# Main.net
KiCad netlist of a schematic drawn in Altium Designer
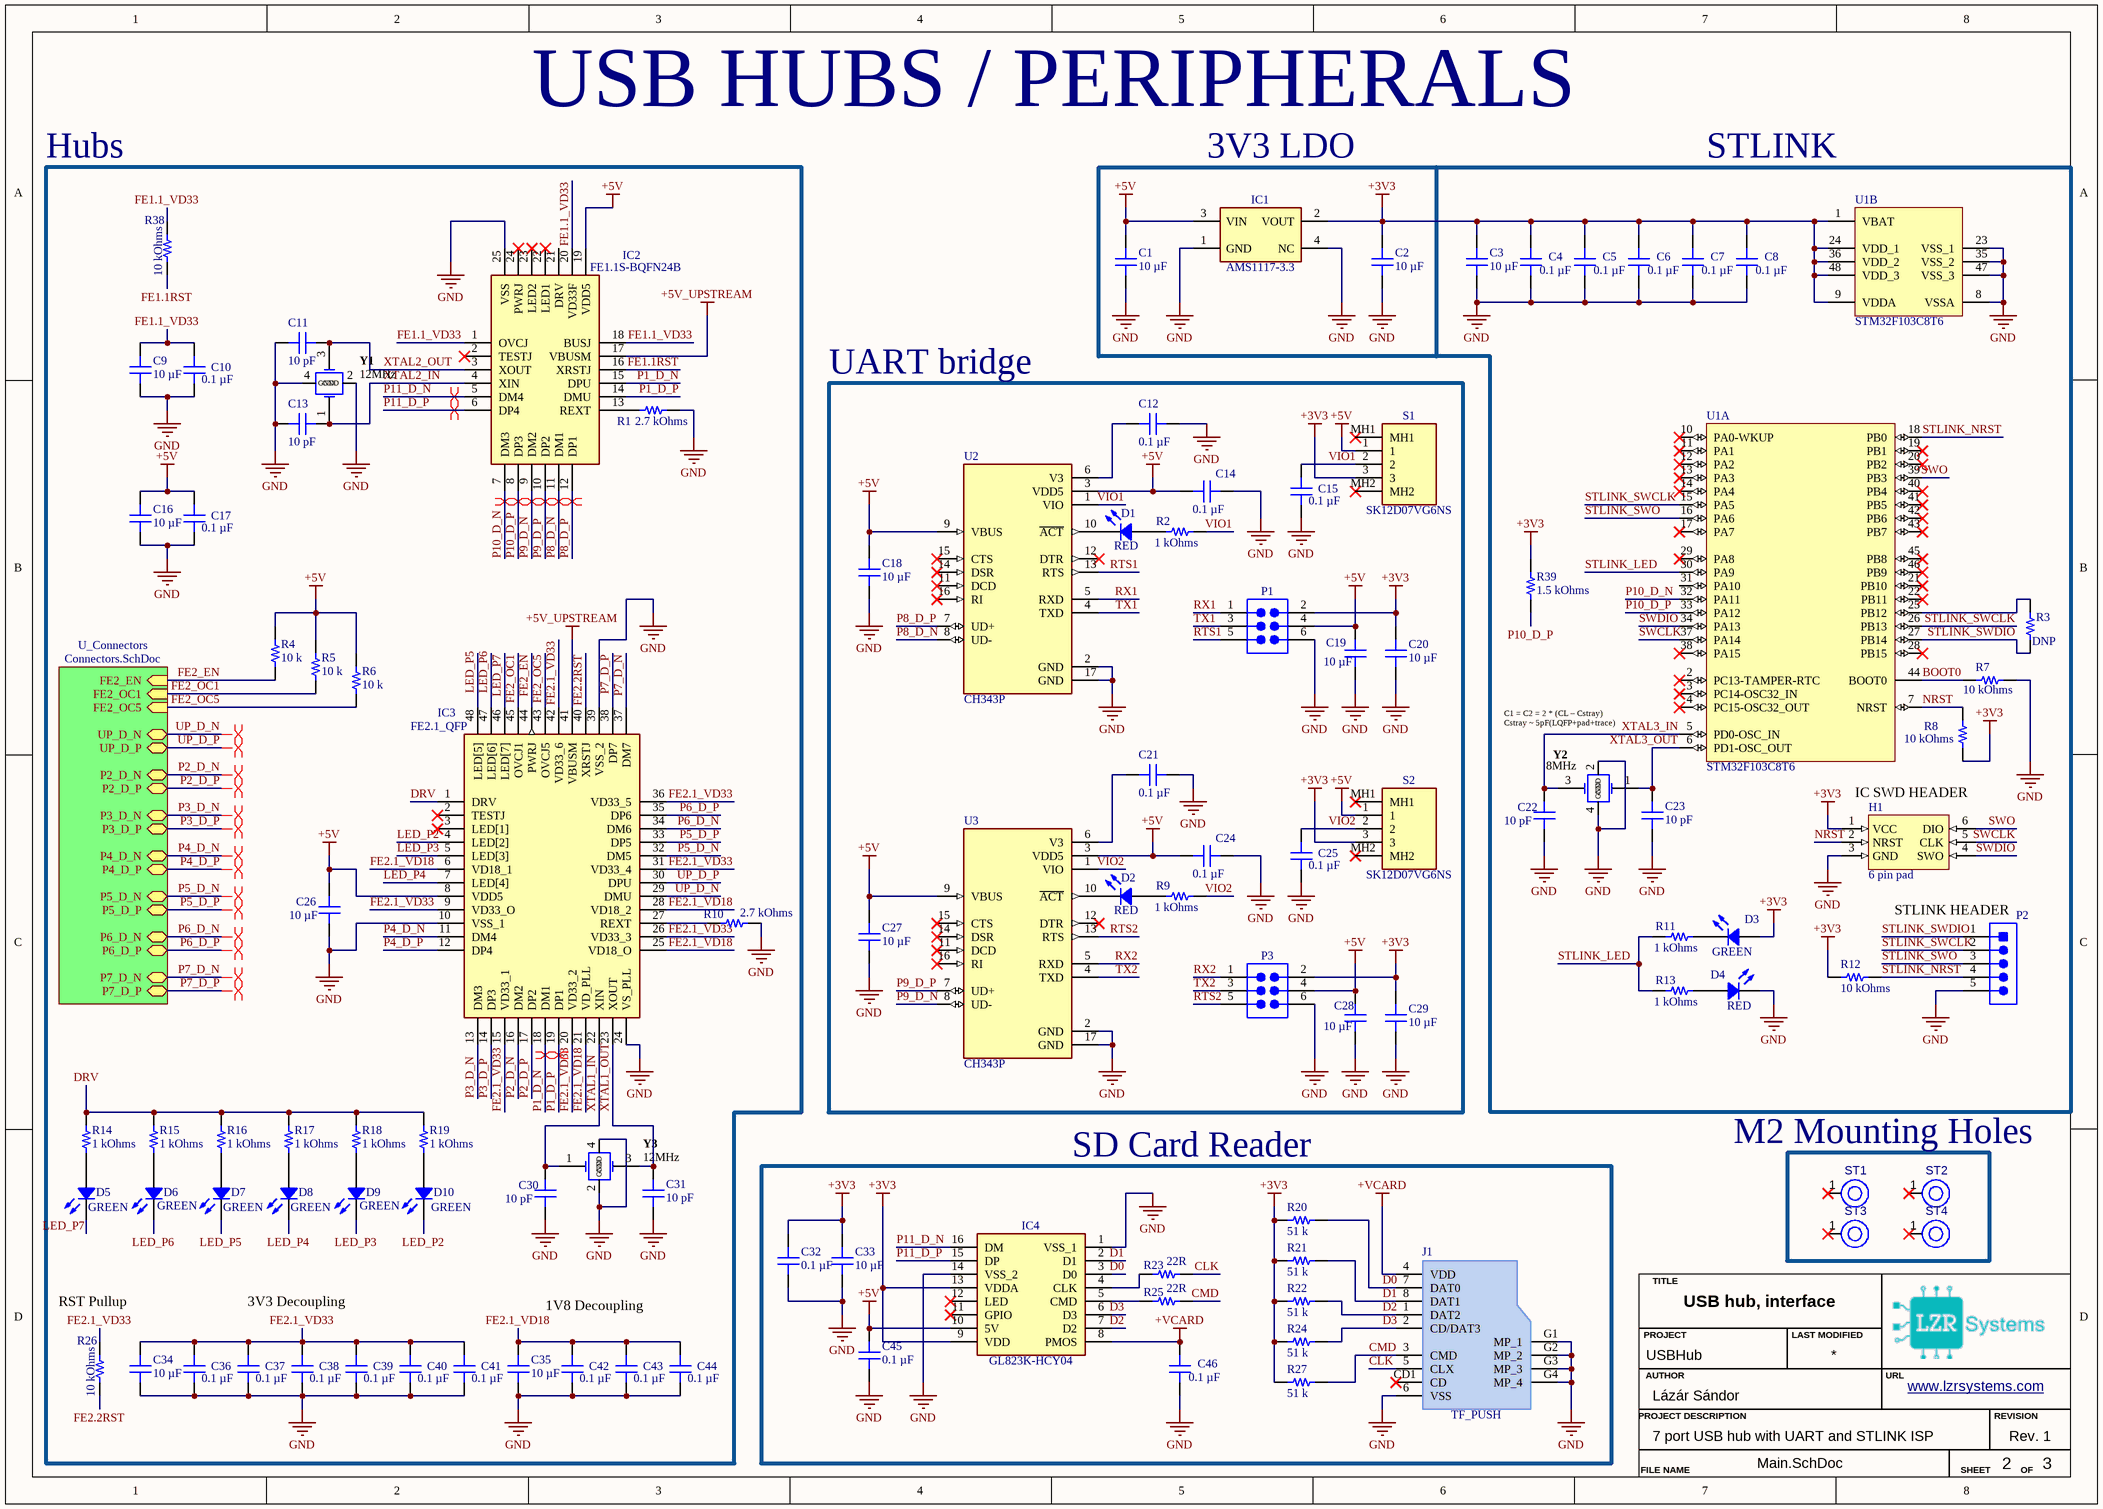
[diagram p0: Main.SchDoc]

(export (version "E")
  (design (tool "Eeschema 10.0.6"))
  (components
    (comp (ref "C1")
      (value "10 µF")
      (footprint "MURATA GRM21B 0805_2012")
      (description "CAP CER 10UF 25V X5R 0805")
      (fields
        (field (name "PART NUMBER") "GRM21BR61E106KA73K")
        (field (name "CAPACITANCE") "10 µF")
        (field (name "MANUFACTURER") "Murata Electronics")
      )
      (libsource (lib "Celestial Altium Library - altium_library") (part "Capacitor"))
    )
    (comp (ref "C2")
      (value "10 µF")
      (footprint "MURATA GRM21B 0805_2012")
      (description "CAP CER 10UF 25V X5R 0805")
      (fields
        (field (name "PART NUMBER") "GRM21BR61E106KA73K")
        (field (name "CAPACITANCE") "10 µF")
        (field (name "MANUFACTURER") "Murata Electronics")
      )
      (libsource (lib "Celestial Altium Library - altium_library") (part "Capacitor"))
    )
    (comp (ref "C3")
      (value "10 µF")
      (footprint "MURATA GRM21B 0805_2012")
      (description "CAP CER 10UF 25V X5R 0805")
      (fields
        (field (name "PART NUMBER") "GRM21BR61E106KA73K")
        (field (name "CAPACITANCE") "10 µF")
        (field (name "MANUFACTURER") "Murata Electronics")
      )
      (libsource (lib "Celestial Altium Library - altium_library") (part "Capacitor"))
    )
    (comp (ref "C4")
      (value "0.1 µF")
      (footprint "CAP 0603_1608")
      (description "CAP CER 0.1UF 50V X7R 0603")
      (fields
        (field (name "PART NUMBER") "GCJ188R71H104KA12D")
        (field (name "CAPACITANCE") "0.1 µF")
        (field (name "MANUFACTURER") "Murata Electronics")
      )
      (libsource (lib "Celestial Altium Library - altium_library") (part "Capacitor"))
    )
    (comp (ref "C5")
      (value "0.1 µF")
      (footprint "CAP 0603_1608")
      (description "CAP CER 0.1UF 50V X7R 0603")
      (fields
        (field (name "PART NUMBER") "GCJ188R71H104KA12D")
        (field (name "CAPACITANCE") "0.1 µF")
        (field (name "MANUFACTURER") "Murata Electronics")
      )
      (libsource (lib "Celestial Altium Library - altium_library") (part "Capacitor"))
    )
    (comp (ref "C6")
      (value "0.1 µF")
      (footprint "CAP 0603_1608")
      (description "CAP CER 0.1UF 50V X7R 0603")
      (fields
        (field (name "PART NUMBER") "GCJ188R71H104KA12D")
        (field (name "CAPACITANCE") "0.1 µF")
        (field (name "MANUFACTURER") "Murata Electronics")
      )
      (libsource (lib "Celestial Altium Library - altium_library") (part "Capacitor"))
    )
    (comp (ref "C7")
      (value "0.1 µF")
      (footprint "CAP 0603_1608")
      (description "CAP CER 0.1UF 50V X7R 0603")
      (fields
        (field (name "PART NUMBER") "GCJ188R71H104KA12D")
        (field (name "CAPACITANCE") "0.1 µF")
        (field (name "MANUFACTURER") "Murata Electronics")
      )
      (libsource (lib "Celestial Altium Library - altium_library") (part "Capacitor"))
    )
    (comp (ref "C8")
      (value "0.1 µF")
      (footprint "CAP 0603_1608")
      (description "CAP CER 0.1UF 50V X7R 0603")
      (fields
        (field (name "PART NUMBER") "GCJ188R71H104KA12D")
        (field (name "CAPACITANCE") "0.1 µF")
        (field (name "MANUFACTURER") "Murata Electronics")
      )
      (libsource (lib "Celestial Altium Library - altium_library") (part "Capacitor"))
    )
    (comp (ref "C9")
      (value "10 µF")
      (footprint "MURATA GRM21B 0805_2012")
      (description "CAP CER 10UF 25V X5R 0805")
      (fields
        (field (name "PART NUMBER") "GRM21BR61E106KA73K")
        (field (name "CAPACITANCE") "10 µF")
        (field (name "MANUFACTURER") "Murata Electronics")
      )
      (libsource (lib "Celestial Altium Library - altium_library") (part "Capacitor"))
    )
    (comp (ref "C10")
      (value "0.1 µF")
      (footprint "CAP 0603_1608")
      (description "CAP CER 0.1UF 50V X7R 0603")
      (fields
        (field (name "PART NUMBER") "GCJ188R71H104KA12D")
        (field (name "CAPACITANCE") "0.1 µF")
        (field (name "MANUFACTURER") "Murata Electronics")
      )
      (libsource (lib "Celestial Altium Library - altium_library") (part "Capacitor"))
    )
    (comp (ref "C11")
      (value "10 pF")
      (footprint "MURATA GCM188 0603_1608")
      (description "CAP CER 10PF 100V C0G/NP0 0603")
      (fields
        (field (name "PART NUMBER") "GCM1885C2A100FA16D")
        (field (name "CAPACITANCE") "10 pF")
        (field (name "MANUFACTURER") "Murata Electronics")
      )
      (libsource (lib "Celestial Altium Library - altium_library") (part "Capacitor"))
    )
    (comp (ref "C12")
      (value "0.1 µF")
      (footprint "CAP 0603_1608")
      (description "CAP CER 0.1UF 50V X7R 0603")
      (fields
        (field (name "PART NUMBER") "GCJ188R71H104KA12D")
        (field (name "CAPACITANCE") "0.1 µF")
        (field (name "MANUFACTURER") "Murata Electronics")
      )
      (libsource (lib "Celestial Altium Library - altium_library") (part "Capacitor"))
    )
    (comp (ref "C13")
      (value "10 pF")
      (footprint "MURATA GCM188 0603_1608")
      (description "CAP CER 10PF 100V C0G/NP0 0603")
      (fields
        (field (name "PART NUMBER") "GCM1885C2A100FA16D")
        (field (name "CAPACITANCE") "10 pF")
        (field (name "MANUFACTURER") "Murata Electronics")
      )
      (libsource (lib "Celestial Altium Library - altium_library") (part "Capacitor"))
    )
    (comp (ref "C14")
      (value "0.1 µF")
      (footprint "CAP 0603_1608")
      (description "CAP CER 0.1UF 50V X7R 0603")
      (fields
        (field (name "PART NUMBER") "GCJ188R71H104KA12D")
        (field (name "CAPACITANCE") "0.1 µF")
        (field (name "MANUFACTURER") "Murata Electronics")
      )
      (libsource (lib "Celestial Altium Library - altium_library") (part "Capacitor"))
    )
    (comp (ref "C15")
      (value "0.1 µF")
      (footprint "CAP 0603_1608")
      (description "CAP CER 0.1UF 50V X7R 0603")
      (fields
        (field (name "PART NUMBER") "GCJ188R71H104KA12D")
        (field (name "CAPACITANCE") "0.1 µF")
        (field (name "MANUFACTURER") "Murata Electronics")
      )
      (libsource (lib "Celestial Altium Library - altium_library") (part "Capacitor"))
    )
    (comp (ref "C16")
      (value "10 µF")
      (footprint "MURATA GRM21B 0805_2012")
      (description "CAP CER 10UF 25V X5R 0805")
      (fields
        (field (name "PART NUMBER") "GRM21BR61E106KA73K")
        (field (name "CAPACITANCE") "10 µF")
        (field (name "MANUFACTURER") "Murata Electronics")
      )
      (libsource (lib "Celestial Altium Library - altium_library") (part "Capacitor"))
    )
    (comp (ref "C17")
      (value "0.1 µF")
      (footprint "CAP 0603_1608")
      (description "CAP CER 0.1UF 50V X7R 0603")
      (fields
        (field (name "PART NUMBER") "GCJ188R71H104KA12D")
        (field (name "CAPACITANCE") "0.1 µF")
        (field (name "MANUFACTURER") "Murata Electronics")
      )
      (libsource (lib "Celestial Altium Library - altium_library") (part "Capacitor"))
    )
    (comp (ref "C18")
      (value "10 µF")
      (footprint "MURATA GRM21B 0805_2012")
      (description "CAP CER 10UF 25V X5R 0805")
      (fields
        (field (name "PART NUMBER") "GRM21BR61E106KA73K")
        (field (name "CAPACITANCE") "10 µF")
        (field (name "MANUFACTURER") "Murata Electronics")
      )
      (libsource (lib "Celestial Altium Library - altium_library") (part "Capacitor"))
    )
    (comp (ref "C19")
      (value "10 µF")
      (footprint "MURATA GRM21B 0805_2012")
      (description "CAP CER 10UF 25V X5R 0805")
      (fields
        (field (name "PART NUMBER") "GRM21BR61E106KA73K")
        (field (name "CAPACITANCE") "10 µF")
        (field (name "MANUFACTURER") "Murata Electronics")
      )
      (libsource (lib "Celestial Altium Library - altium_library") (part "Capacitor"))
    )
    (comp (ref "C20")
      (value "10 µF")
      (footprint "MURATA GRM21B 0805_2012")
      (description "CAP CER 10UF 25V X5R 0805")
      (fields
        (field (name "PART NUMBER") "GRM21BR61E106KA73K")
        (field (name "CAPACITANCE") "10 µF")
        (field (name "MANUFACTURER") "Murata Electronics")
      )
      (libsource (lib "Celestial Altium Library - altium_library") (part "Capacitor"))
    )
    (comp (ref "C21")
      (value "0.1 µF")
      (footprint "CAP 0603_1608")
      (description "CAP CER 0.1UF 50V X7R 0603")
      (fields
        (field (name "PART NUMBER") "GCJ188R71H104KA12D")
        (field (name "CAPACITANCE") "0.1 µF")
        (field (name "MANUFACTURER") "Murata Electronics")
      )
      (libsource (lib "Celestial Altium Library - altium_library") (part "Capacitor"))
    )
    (comp (ref "C22")
      (value "10 pF")
      (footprint "MURATA GCM188 0603_1608")
      (description "CAP CER 10PF 100V C0G/NP0 0603")
      (fields
        (field (name "PART NUMBER") "GCM1885C2A100FA16D")
        (field (name "CAPACITANCE") "10 pF")
        (field (name "MANUFACTURER") "Murata Electronics")
      )
      (libsource (lib "Celestial Altium Library - altium_library") (part "Capacitor"))
    )
    (comp (ref "C23")
      (value "10 pF")
      (footprint "MURATA GCM188 0603_1608")
      (description "CAP CER 10PF 100V C0G/NP0 0603")
      (fields
        (field (name "PART NUMBER") "GCM1885C2A100FA16D")
        (field (name "CAPACITANCE") "10 pF")
        (field (name "MANUFACTURER") "Murata Electronics")
      )
      (libsource (lib "Celestial Altium Library - altium_library") (part "Capacitor"))
    )
    (comp (ref "C24")
      (value "0.1 µF")
      (footprint "CAP 0603_1608")
      (description "CAP CER 0.1UF 50V X7R 0603")
      (fields
        (field (name "PART NUMBER") "GCJ188R71H104KA12D")
        (field (name "CAPACITANCE") "0.1 µF")
        (field (name "MANUFACTURER") "Murata Electronics")
      )
      (libsource (lib "Celestial Altium Library - altium_library") (part "Capacitor"))
    )
    (comp (ref "C25")
      (value "0.1 µF")
      (footprint "CAP 0603_1608")
      (description "CAP CER 0.1UF 50V X7R 0603")
      (fields
        (field (name "PART NUMBER") "GCJ188R71H104KA12D")
        (field (name "CAPACITANCE") "0.1 µF")
        (field (name "MANUFACTURER") "Murata Electronics")
      )
      (libsource (lib "Celestial Altium Library - altium_library") (part "Capacitor"))
    )
    (comp (ref "C26")
      (value "10 µF")
      (footprint "MURATA GRM21B 0805_2012")
      (description "CAP CER 10UF 25V X5R 0805")
      (fields
        (field (name "PART NUMBER") "GRM21BR61E106KA73K")
        (field (name "CAPACITANCE") "10 µF")
        (field (name "MANUFACTURER") "Murata Electronics")
      )
      (libsource (lib "Celestial Altium Library - altium_library") (part "Capacitor"))
    )
    (comp (ref "C27")
      (value "10 µF")
      (footprint "MURATA GRM21B 0805_2012")
      (description "CAP CER 10UF 25V X5R 0805")
      (fields
        (field (name "PART NUMBER") "GRM21BR61E106KA73K")
        (field (name "CAPACITANCE") "10 µF")
        (field (name "MANUFACTURER") "Murata Electronics")
      )
      (libsource (lib "Celestial Altium Library - altium_library") (part "Capacitor"))
    )
    (comp (ref "C28")
      (value "10 µF")
      (footprint "MURATA GRM21B 0805_2012")
      (description "CAP CER 10UF 25V X5R 0805")
      (fields
        (field (name "PART NUMBER") "GRM21BR61E106KA73K")
        (field (name "CAPACITANCE") "10 µF")
        (field (name "MANUFACTURER") "Murata Electronics")
      )
      (libsource (lib "Celestial Altium Library - altium_library") (part "Capacitor"))
    )
    (comp (ref "C29")
      (value "10 µF")
      (footprint "MURATA GRM21B 0805_2012")
      (description "CAP CER 10UF 25V X5R 0805")
      (fields
        (field (name "PART NUMBER") "GRM21BR61E106KA73K")
        (field (name "CAPACITANCE") "10 µF")
        (field (name "MANUFACTURER") "Murata Electronics")
      )
      (libsource (lib "Celestial Altium Library - altium_library") (part "Capacitor"))
    )
    (comp (ref "C30")
      (value "10 pF")
      (footprint "MURATA GCM188 0603_1608")
      (description "CAP CER 10PF 100V C0G/NP0 0603")
      (fields
        (field (name "PART NUMBER") "GCM1885C2A100FA16D")
        (field (name "CAPACITANCE") "10 pF")
        (field (name "MANUFACTURER") "Murata Electronics")
      )
      (libsource (lib "Celestial Altium Library - altium_library") (part "Capacitor"))
    )
    (comp (ref "C31")
      (value "10 pF")
      (footprint "MURATA GCM188 0603_1608")
      (description "CAP CER 10PF 100V C0G/NP0 0603")
      (fields
        (field (name "PART NUMBER") "GCM1885C2A100FA16D")
        (field (name "CAPACITANCE") "10 pF")
        (field (name "MANUFACTURER") "Murata Electronics")
      )
      (libsource (lib "Celestial Altium Library - altium_library") (part "Capacitor"))
    )
    (comp (ref "C32")
      (value "0.1 µF")
      (footprint "CAP 0603_1608")
      (description "CAP CER 0.1UF 50V X7R 0603")
      (fields
        (field (name "PART NUMBER") "GCJ188R71H104KA12D")
        (field (name "CAPACITANCE") "0.1 µF")
        (field (name "MANUFACTURER") "Murata Electronics")
      )
      (libsource (lib "Celestial Altium Library - altium_library") (part "Capacitor"))
    )
    (comp (ref "C33")
      (value "10 µF")
      (footprint "MURATA GRM21B 0805_2012")
      (description "CAP CER 10UF 25V X5R 0805")
      (fields
        (field (name "PART NUMBER") "GRM21BR61E106KA73K")
        (field (name "CAPACITANCE") "10 µF")
        (field (name "MANUFACTURER") "Murata Electronics")
      )
      (libsource (lib "Celestial Altium Library - altium_library") (part "Capacitor"))
    )
    (comp (ref "C34")
      (value "10 µF")
      (footprint "MURATA GRM21B 0805_2012")
      (description "CAP CER 10UF 25V X5R 0805")
      (fields
        (field (name "PART NUMBER") "GRM21BR61E106KA73K")
        (field (name "CAPACITANCE") "10 µF")
        (field (name "MANUFACTURER") "Murata Electronics")
      )
      (libsource (lib "Celestial Altium Library - altium_library") (part "Capacitor"))
    )
    (comp (ref "C35")
      (value "10 µF")
      (footprint "MURATA GRM21B 0805_2012")
      (description "CAP CER 10UF 25V X5R 0805")
      (fields
        (field (name "PART NUMBER") "GRM21BR61E106KA73K")
        (field (name "CAPACITANCE") "10 µF")
        (field (name "MANUFACTURER") "Murata Electronics")
      )
      (libsource (lib "Celestial Altium Library - altium_library") (part "Capacitor"))
    )
    (comp (ref "C36")
      (value "0.1 µF")
      (footprint "CAP 0603_1608")
      (description "CAP CER 0.1UF 50V X7R 0603")
      (fields
        (field (name "PART NUMBER") "GCJ188R71H104KA12D")
        (field (name "CAPACITANCE") "0.1 µF")
        (field (name "MANUFACTURER") "Murata Electronics")
      )
      (libsource (lib "Celestial Altium Library - altium_library") (part "Capacitor"))
    )
    (comp (ref "C37")
      (value "0.1 µF")
      (footprint "CAP 0603_1608")
      (description "CAP CER 0.1UF 50V X7R 0603")
      (fields
        (field (name "PART NUMBER") "GCJ188R71H104KA12D")
        (field (name "CAPACITANCE") "0.1 µF")
        (field (name "MANUFACTURER") "Murata Electronics")
      )
      (libsource (lib "Celestial Altium Library - altium_library") (part "Capacitor"))
    )
    (comp (ref "C38")
      (value "0.1 µF")
      (footprint "CAP 0603_1608")
      (description "CAP CER 0.1UF 50V X7R 0603")
      (fields
        (field (name "PART NUMBER") "GCJ188R71H104KA12D")
        (field (name "CAPACITANCE") "0.1 µF")
        (field (name "MANUFACTURER") "Murata Electronics")
      )
      (libsource (lib "Celestial Altium Library - altium_library") (part "Capacitor"))
    )
    (comp (ref "C39")
      (value "0.1 µF")
      (footprint "CAP 0603_1608")
      (description "CAP CER 0.1UF 50V X7R 0603")
      (fields
        (field (name "PART NUMBER") "GCJ188R71H104KA12D")
        (field (name "CAPACITANCE") "0.1 µF")
        (field (name "MANUFACTURER") "Murata Electronics")
      )
      (libsource (lib "Celestial Altium Library - altium_library") (part "Capacitor"))
    )
    (comp (ref "C40")
      (value "0.1 µF")
      (footprint "CAP 0603_1608")
      (description "CAP CER 0.1UF 50V X7R 0603")
      (fields
        (field (name "PART NUMBER") "GCJ188R71H104KA12D")
        (field (name "CAPACITANCE") "0.1 µF")
        (field (name "MANUFACTURER") "Murata Electronics")
      )
      (libsource (lib "Celestial Altium Library - altium_library") (part "Capacitor"))
    )
    (comp (ref "C41")
      (value "0.1 µF")
      (footprint "CAP 0603_1608")
      (description "CAP CER 0.1UF 50V X7R 0603")
      (fields
        (field (name "PART NUMBER") "GCJ188R71H104KA12D")
        (field (name "CAPACITANCE") "0.1 µF")
        (field (name "MANUFACTURER") "Murata Electronics")
      )
      (libsource (lib "Celestial Altium Library - altium_library") (part "Capacitor"))
    )
    (comp (ref "C42")
      (value "0.1 µF")
      (footprint "CAP 0603_1608")
      (description "CAP CER 0.1UF 50V X7R 0603")
      (fields
        (field (name "PART NUMBER") "GCJ188R71H104KA12D")
        (field (name "CAPACITANCE") "0.1 µF")
        (field (name "MANUFACTURER") "Murata Electronics")
      )
      (libsource (lib "Celestial Altium Library - altium_library") (part "Capacitor"))
    )
    (comp (ref "C43")
      (value "0.1 µF")
      (footprint "CAP 0603_1608")
      (description "CAP CER 0.1UF 50V X7R 0603")
      (fields
        (field (name "PART NUMBER") "GCJ188R71H104KA12D")
        (field (name "CAPACITANCE") "0.1 µF")
        (field (name "MANUFACTURER") "Murata Electronics")
      )
      (libsource (lib "Celestial Altium Library - altium_library") (part "Capacitor"))
    )
    (comp (ref "C44")
      (value "0.1 µF")
      (footprint "CAP 0603_1608")
      (description "CAP CER 0.1UF 50V X7R 0603")
      (fields
        (field (name "PART NUMBER") "GCJ188R71H104KA12D")
        (field (name "CAPACITANCE") "0.1 µF")
        (field (name "MANUFACTURER") "Murata Electronics")
      )
      (libsource (lib "Celestial Altium Library - altium_library") (part "Capacitor"))
    )
    (comp (ref "C45")
      (value "0.1 µF")
      (footprint "CAP 0603_1608")
      (description "CAP CER 0.1UF 50V X7R 0603")
      (fields
        (field (name "PART NUMBER") "GCJ188R71H104KA12D")
        (field (name "CAPACITANCE") "0.1 µF")
        (field (name "MANUFACTURER") "Murata Electronics")
      )
      (libsource (lib "Celestial Altium Library - altium_library") (part "Capacitor"))
    )
    (comp (ref "C46")
      (value "0.1 µF")
      (footprint "CAP 0603_1608")
      (description "CAP CER 0.1UF 50V X7R 0603")
      (fields
        (field (name "PART NUMBER") "GCJ188R71H104KA12D")
        (field (name "CAPACITANCE") "0.1 µF")
        (field (name "MANUFACTURER") "Murata Electronics")
      )
      (libsource (lib "Celestial Altium Library - altium_library") (part "Capacitor"))
    )
    (comp (ref "D1")
      (value "RED")
      (footprint "LED 0603_1608 RED")
      (description "LED RED DIFFUSED 0603 SMD")
      (fields
        (field (name "PART NUMBER") "B1931URO-20D000114U1930")
        (field (name "MANUFACTURER") "Harvatek Corporation")
      )
      (libsource (lib "Celestial Altium Library - altium_library") (part "LED"))
    )
    (comp (ref "D2")
      (value "RED")
      (footprint "LED 0603_1608 RED")
      (description "LED RED DIFFUSED 0603 SMD")
      (fields
        (field (name "PART NUMBER") "B1931URO-20D000114U1930")
        (field (name "MANUFACTURER") "Harvatek Corporation")
      )
      (libsource (lib "Celestial Altium Library - altium_library") (part "LED"))
    )
    (comp (ref "D3")
      (value "GREEN")
      (footprint "LED 0603_1608 RED")
      (description "LED RED DIFFUSED 0603 SMD")
      (fields
        (field (name "PART NUMBER") "B1931URO-20D000114U1930")
        (field (name "MANUFACTURER") "Harvatek Corporation")
      )
      (libsource (lib "Celestial Altium Library - altium_library") (part "LED"))
    )
    (comp (ref "D4")
      (value "RED")
      (footprint "LED 0603_1608 RED")
      (description "LED RED DIFFUSED 0603 SMD")
      (fields
        (field (name "PART NUMBER") "B1931URO-20D000114U1930")
        (field (name "MANUFACTURER") "Harvatek Corporation")
      )
      (libsource (lib "Celestial Altium Library - altium_library") (part "LED"))
    )
    (comp (ref "D5")
      (value "GREEN")
      (footprint "LED 0603_1608 RED")
      (description "LED RED DIFFUSED 0603 SMD")
      (fields
        (field (name "PART NUMBER") "B1931URO-20D000114U1930")
        (field (name "MANUFACTURER") "Harvatek Corporation")
      )
      (libsource (lib "Celestial Altium Library - altium_library") (part "LED"))
    )
    (comp (ref "D6")
      (value "GREEN")
      (footprint "LED 0603_1608 RED")
      (description "LED RED DIFFUSED 0603 SMD")
      (fields
        (field (name "PART NUMBER") "B1931URO-20D000114U1930")
        (field (name "MANUFACTURER") "Harvatek Corporation")
      )
      (libsource (lib "Celestial Altium Library - altium_library") (part "LED"))
    )
    (comp (ref "D7")
      (value "GREEN")
      (footprint "LED 0603_1608 RED")
      (description "LED RED DIFFUSED 0603 SMD")
      (fields
        (field (name "PART NUMBER") "B1931URO-20D000114U1930")
        (field (name "MANUFACTURER") "Harvatek Corporation")
      )
      (libsource (lib "Celestial Altium Library - altium_library") (part "LED"))
    )
    (comp (ref "D8")
      (value "GREEN")
      (footprint "LED 0603_1608 RED")
      (description "LED RED DIFFUSED 0603 SMD")
      (fields
        (field (name "PART NUMBER") "B1931URO-20D000114U1930")
        (field (name "MANUFACTURER") "Harvatek Corporation")
      )
      (libsource (lib "Celestial Altium Library - altium_library") (part "LED"))
    )
    (comp (ref "D9")
      (value "GREEN")
      (footprint "LED 0603_1608 RED")
      (description "LED RED DIFFUSED 0603 SMD")
      (fields
        (field (name "PART NUMBER") "B1931URO-20D000114U1930")
        (field (name "MANUFACTURER") "Harvatek Corporation")
      )
      (libsource (lib "Celestial Altium Library - altium_library") (part "LED"))
    )
    (comp (ref "D10")
      (value "GREEN")
      (footprint "LED 0603_1608 RED")
      (description "LED RED DIFFUSED 0603 SMD")
      (fields
        (field (name "PART NUMBER") "B1931URO-20D000114U1930")
        (field (name "MANUFACTURER") "Harvatek Corporation")
      )
      (libsource (lib "Celestial Altium Library - altium_library") (part "LED"))
    )
    (comp (ref "H1")
      (value "6 pin pad")
      (footprint "6 pin pad-Footprint-1")
      (libsource (lib "Sandor Lazar") (part "SWD-1.27mm-2x03"))
    )
    (comp (ref "IC1")
      (value "AMS1117-3.3")
      (footprint "SamacSys:SOT229P700X180-4N")
      (description "Integrated Circuit")
      (libsource (lib "SamacSys") (part "AMS1117-3.3"))
    )
    (comp (ref "IC2")
      (value "FE1.1S-BQFN24B")
      (footprint "SamacSys:QFN50P400X400X80-25N-D")
      (description "Integrated Circuit")
      (libsource (lib "*") (part "FE1.1S-BQFN24B"))
    )
    (comp (ref "IC3")
      (value "FE2.1_QFP")
      (footprint "SamacSys:QFP50P900X900X160-48N")
      (description "Integrated Circuit")
      (libsource (lib "*") (part "FE2.1_QFP"))
    )
    (comp (ref "IC4")
      (value "GL823K-HCY04")
      (footprint "SamacSys:SOP64P600X175-16N")
      (description "Integrated Circuit")
      (libsource (lib "*") (part "GL823K-HCY04"))
    )
    (comp (ref "J1")
      (value "TF_PUSH")
      (footprint "SamacSys:TFPUSH")
      (description "Connector")
      (fields (field (name "MANUFACTURER_PART_NUMBER") "TF PUSH"))
      (libsource (lib "SamacSys") (part "TF_PUSH"))
    )
    (comp (ref "P1")
      (value "MTLW-103-06-G-D-180")
      (footprint "SMTC-MTLW-103-06-X-D-180")
      (description "Pin Header, Board-to-Board, 2.54 mm, 2 Rows, 6 Contacts, Through Hole, MTLW Series")
      (libsource (lib "Sandor Lazar") (part "SMTC-MTLW-103-06-X-D-180"))
    )
    (comp (ref "P2")
      (value "77311-462K05LF")
      (footprint "FCI-77311-5_V")
      (fields (field (name "MANUFACTURER") "FCI Electronics"))
      (libsource (lib "Sandor Lazar") (part "CN-1P-M-R5"))
    )
    (comp (ref "P3")
      (value "MTLW-103-06-G-D-180")
      (footprint "SMTC-MTLW-103-06-X-D-180")
      (description "Pin Header, Board-to-Board, 2.54 mm, 2 Rows, 6 Contacts, Through Hole, MTLW Series")
      (libsource (lib "Sandor Lazar") (part "SMTC-MTLW-103-06-X-D-180"))
    )
    (comp (ref "R1")
      (value "2.7 kOhms")
      (footprint "RES 0805_2012")
      (description "RES 2.7K OHM 0.1% 1/5W 0805")
      (fields
        (field (name "PART NUMBER") "RTAN0805BKE2K70")
        (field (name "MANUFACTURER") "Stackpole Electronics Inc")
      )
      (libsource (lib "Celestial Altium Library - altium_library") (part "Resistor"))
    )
    (comp (ref "R2")
      (value "1 kOhms")
      (footprint "YAGEO RES 0603_1608")
      (description "RES SMD 1K OHM 1% 1/10W 0603")
      (fields (field (name "PART NUMBER") "RT0603FRE071KL") (field (name "MANUFACTURER") "Yageo"))
      (libsource (lib "Celestial Altium Library - altium_library") (part "Resistor"))
    )
    (comp (ref "R3")
      (value "DNP")
      (footprint "YAGEO RES 0603_1608")
      (description "RES SMD 1K OHM 1% 1/10W 0603")
      (fields (field (name "PART NUMBER") "RT0603FRE071KL") (field (name "MANUFACTURER") "Yageo"))
      (libsource (lib "Celestial Altium Library - altium_library") (part "Resistor"))
    )
    (comp (ref "R4")
      (value "10 k")
      (footprint "RES 0603_1608")
      (description "RES 10K OHM 5% 1/10W 0603")
      (fields (field (name "PART NUMBER") "CRCW060310K0JNEAC") (field (name "MANUFACTURER") "Vishay Dale"))
      (libsource (lib "Celestial Altium Library - altium_library") (part "Resistor"))
    )
    (comp (ref "R5")
      (value "10 k")
      (footprint "RES 0603_1608")
      (description "RES 10K OHM 5% 1/10W 0603")
      (fields (field (name "PART NUMBER") "CRCW060310K0JNEAC") (field (name "MANUFACTURER") "Vishay Dale"))
      (libsource (lib "Celestial Altium Library - altium_library") (part "Resistor"))
    )
    (comp (ref "R6")
      (value "10 k")
      (footprint "RES 0603_1608")
      (description "RES 10K OHM 5% 1/10W 0603")
      (fields (field (name "PART NUMBER") "CRCW060310K0JNEAC") (field (name "MANUFACTURER") "Vishay Dale"))
      (libsource (lib "Celestial Altium Library - altium_library") (part "Resistor"))
    )
    (comp (ref "R7")
      (value "10 kOhms")
      (footprint "RES 0603_1608")
      (description "RES 10K OHM 5% 1/10W 0603")
      (fields (field (name "PART NUMBER") "CRCW060310K0JNEAC") (field (name "MANUFACTURER") "Vishay Dale"))
      (libsource (lib "Celestial Altium Library - altium_library") (part "Resistor"))
    )
    (comp (ref "R8")
      (value "10 kOhms")
      (footprint "RES 0603_1608")
      (description "RES 10K OHM 5% 1/10W 0603")
      (fields (field (name "PART NUMBER") "CRCW060310K0JNEAC") (field (name "MANUFACTURER") "Vishay Dale"))
      (libsource (lib "Celestial Altium Library - altium_library") (part "Resistor"))
    )
    (comp (ref "R9")
      (value "1 kOhms")
      (footprint "YAGEO RES 0603_1608")
      (description "RES SMD 1K OHM 1% 1/10W 0603")
      (fields (field (name "PART NUMBER") "RT0603FRE071KL") (field (name "MANUFACTURER") "Yageo"))
      (libsource (lib "Celestial Altium Library - altium_library") (part "Resistor"))
    )
    (comp (ref "R10")
      (value "2.7 kOhms")
      (footprint "RES 0805_2012")
      (description "RES 2.7K OHM 0.1% 1/5W 0805")
      (fields
        (field (name "PART NUMBER") "RTAN0805BKE2K70")
        (field (name "MANUFACTURER") "Stackpole Electronics Inc")
      )
      (libsource (lib "Celestial Altium Library - altium_library") (part "Resistor"))
    )
    (comp (ref "R11")
      (value "1 kOhms")
      (footprint "YAGEO RES 0603_1608")
      (description "RES SMD 1K OHM 1% 1/10W 0603")
      (fields (field (name "PART NUMBER") "RT0603FRE071KL") (field (name "MANUFACTURER") "Yageo"))
      (libsource (lib "Celestial Altium Library - altium_library") (part "Resistor"))
    )
    (comp (ref "R12")
      (value "10 kOhms")
      (footprint "RES 0603_1608")
      (description "RES 10K OHM 5% 1/10W 0603")
      (fields (field (name "PART NUMBER") "CRCW060310K0JNEAC") (field (name "MANUFACTURER") "Vishay Dale"))
      (libsource (lib "Celestial Altium Library - altium_library") (part "Resistor"))
    )
    (comp (ref "R13")
      (value "1 kOhms")
      (footprint "YAGEO RES 0603_1608")
      (description "RES SMD 1K OHM 1% 1/10W 0603")
      (fields (field (name "PART NUMBER") "RT0603FRE071KL") (field (name "MANUFACTURER") "Yageo"))
      (libsource (lib "Celestial Altium Library - altium_library") (part "Resistor"))
    )
    (comp (ref "R14")
      (value "1 kOhms")
      (footprint "YAGEO RES 0603_1608")
      (description "RES SMD 1K OHM 1% 1/10W 0603")
      (fields (field (name "PART NUMBER") "RT0603FRE071KL") (field (name "MANUFACTURER") "Yageo"))
      (libsource (lib "Celestial Altium Library - altium_library") (part "Resistor"))
    )
    (comp (ref "R15")
      (value "1 kOhms")
      (footprint "YAGEO RES 0603_1608")
      (description "RES SMD 1K OHM 1% 1/10W 0603")
      (fields (field (name "PART NUMBER") "RT0603FRE071KL") (field (name "MANUFACTURER") "Yageo"))
      (libsource (lib "Celestial Altium Library - altium_library") (part "Resistor"))
    )
    (comp (ref "R16")
      (value "1 kOhms")
      (footprint "YAGEO RES 0603_1608")
      (description "RES SMD 1K OHM 1% 1/10W 0603")
      (fields (field (name "PART NUMBER") "RT0603FRE071KL") (field (name "MANUFACTURER") "Yageo"))
      (libsource (lib "Celestial Altium Library - altium_library") (part "Resistor"))
    )
    (comp (ref "R17")
      (value "1 kOhms")
      (footprint "YAGEO RES 0603_1608")
      (description "RES SMD 1K OHM 1% 1/10W 0603")
      (fields (field (name "PART NUMBER") "RT0603FRE071KL") (field (name "MANUFACTURER") "Yageo"))
      (libsource (lib "Celestial Altium Library - altium_library") (part "Resistor"))
    )
    (comp (ref "R18")
      (value "1 kOhms")
      (footprint "YAGEO RES 0603_1608")
      (description "RES SMD 1K OHM 1% 1/10W 0603")
      (fields (field (name "PART NUMBER") "RT0603FRE071KL") (field (name "MANUFACTURER") "Yageo"))
      (libsource (lib "Celestial Altium Library - altium_library") (part "Resistor"))
    )
    (comp (ref "R19")
      (value "1 kOhms")
      (footprint "YAGEO RES 0603_1608")
      (description "RES SMD 1K OHM 1% 1/10W 0603")
      (fields (field (name "PART NUMBER") "RT0603FRE071KL") (field (name "MANUFACTURER") "Yageo"))
      (libsource (lib "Celestial Altium Library - altium_library") (part "Resistor"))
    )
    (comp (ref "R20")
      (value "51 k")
      (footprint "YAGEO RES 0603_1608")
      (description "RES 51K OHM 1% 1/10W 0603")
      (fields (field (name "PART NUMBER") "RC0603FR-0751KL") (field (name "MANUFACTURER") "Yageo"))
      (libsource (lib "Celestial Altium Library - altium_library") (part "Resistor"))
    )
    (comp (ref "R21")
      (value "51 k")
      (footprint "YAGEO RES 0603_1608")
      (description "RES 51K OHM 1% 1/10W 0603")
      (fields (field (name "PART NUMBER") "RC0603FR-0751KL") (field (name "MANUFACTURER") "Yageo"))
      (libsource (lib "Celestial Altium Library - altium_library") (part "Resistor"))
    )
    (comp (ref "R22")
      (value "51 k")
      (footprint "YAGEO RES 0603_1608")
      (description "RES 51K OHM 1% 1/10W 0603")
      (fields (field (name "PART NUMBER") "RC0603FR-0751KL") (field (name "MANUFACTURER") "Yageo"))
      (libsource (lib "Celestial Altium Library - altium_library") (part "Resistor"))
    )
    (comp (ref "R23")
      (value "22R")
      (footprint "RES 0603_1608")
      (description "RES 22 OHM 1% 1/10W 0603")
      (fields
        (field (name "PART NUMBER") "RMCF0603FT22R0")
        (field (name "MANUFACTURER") "Stackpole Electronics Inc")
      )
      (libsource (lib "Celestial Altium Library - altium_library") (part "Resistor"))
    )
    (comp (ref "R24")
      (value "51 k")
      (footprint "YAGEO RES 0603_1608")
      (description "RES 51K OHM 1% 1/10W 0603")
      (fields (field (name "PART NUMBER") "RC0603FR-0751KL") (field (name "MANUFACTURER") "Yageo"))
      (libsource (lib "Celestial Altium Library - altium_library") (part "Resistor"))
    )
    (comp (ref "R25")
      (value "22R")
      (footprint "RES 0603_1608")
      (description "RES 22 OHM 1% 1/10W 0603")
      (fields
        (field (name "PART NUMBER") "RMCF0603FT22R0")
        (field (name "MANUFACTURER") "Stackpole Electronics Inc")
      )
      (libsource (lib "Celestial Altium Library - altium_library") (part "Resistor"))
    )
    (comp (ref "R26")
      (value "10 kOhms")
      (footprint "RES 0603_1608")
      (description "RES 10K OHM 5% 1/10W 0603")
      (fields (field (name "PART NUMBER") "CRCW060310K0JNEAC") (field (name "MANUFACTURER") "Vishay Dale"))
      (libsource (lib "Celestial Altium Library - altium_library") (part "Resistor"))
    )
    (comp (ref "R27")
      (value "51 k")
      (footprint "YAGEO RES 0603_1608")
      (description "RES 51K OHM 1% 1/10W 0603")
      (fields (field (name "PART NUMBER") "RC0603FR-0751KL") (field (name "MANUFACTURER") "Yageo"))
      (libsource (lib "Celestial Altium Library - altium_library") (part "Resistor"))
    )
    (comp (ref "R38")
      (value "10 kOhms")
      (footprint "RES 0603_1608")
      (description "RES 10K OHM 5% 1/10W 0603")
      (fields (field (name "PART NUMBER") "CRCW060310K0JNEAC") (field (name "MANUFACTURER") "Vishay Dale"))
      (libsource (lib "Celestial Altium Library - altium_library") (part "Resistor"))
    )
    (comp (ref "R39")
      (value "1.5 kOhms")
      (footprint "RES 0603_1608")
      (description "RES 1.5K OHM 1% 1/8W 0603")
      (fields
        (field (name "PART NUMBER") "RNCP0603FTD1K50")
        (field (name "MANUFACTURER") "Stackpole Electronics Inc")
      )
      (libsource (lib "Celestial Altium Library - altium_library") (part "Resistor"))
    )
    (comp (ref "S1")
      (value "SK12D07VG6NS")
      (footprint "SamacSys:SK12D07VG6NS")
      (description "Switch")
      (fields (field (name "MOUSER PART NUMBER") "611-SK12D07VG6NS"))
      (libsource (lib "SamacSys") (part "SK12D07VG6NS"))
    )
    (comp (ref "S2")
      (value "SK12D07VG6NS")
      (footprint "SamacSys:SK12D07VG6NS")
      (description "Switch")
      (fields (field (name "MOUSER PART NUMBER") "611-SK12D07VG6NS"))
      (libsource (lib "SamacSys") (part "SK12D07VG6NS"))
    )
    (comp (ref "ST1")
      (value "PTH-M2D5X5")
      (footprint "PTH-M2D5X5")
      (description "M2 PTH (2.5mm), 5mm pad")
      (libsource (lib "Sandor Lazar") (part "CMP-00028-00000-1"))
    )
    (comp (ref "ST2")
      (value "PTH-M2D5X5")
      (footprint "PTH-M2D5X5")
      (description "M2 PTH (2.5mm), 5mm pad")
      (libsource (lib "Sandor Lazar") (part "CMP-00028-00000-1"))
    )
    (comp (ref "ST3")
      (value "PTH-M2D5X5")
      (footprint "PTH-M2D5X5")
      (description "M2 PTH (2.5mm), 5mm pad")
      (libsource (lib "Sandor Lazar") (part "CMP-00028-00000-1"))
    )
    (comp (ref "ST4")
      (value "PTH-M2D5X5")
      (footprint "PTH-M2D5X5")
      (description "M2 PTH (2.5mm), 5mm pad")
      (libsource (lib "Sandor Lazar") (part "CMP-00028-00000-1"))
    )
    (comp (ref "U1")
      (value "STM32F103C8T6")
      (footprint "STM-LQFP48_L")
      (description "RISC Microcontroller, 32-Bit, FLASH, STM32 CPU, 72MHz, CMOS, PQFP48")
      (libsource (lib "Sandor Lazar") (part "MC-ARM-STM32F103X8_B-SQ48"))
    )
    (comp (ref "U2")
      (value "CH343P")
      (footprint "QFN50P300X300X80-17N")
      (description "USB to High-Speed Serial Chip CH343")
      (fields (field (name "MF") "WCH"))
      (libsource (lib "Sandor Lazar") (part "CH343P"))
    )
    (comp (ref "U3")
      (value "CH343P")
      (footprint "QFN50P300X300X80-17N")
      (description "USB to High-Speed Serial Chip CH343")
      (fields (field (name "MF") "WCH"))
      (libsource (lib "Sandor Lazar") (part "CH343P"))
    )
    (comp (ref "Y1")
      (value "12MHz")
      (footprint "Yajingxin TX32258M4DBDD2T-Footprint-1")
      (description "8 MHz crystal, CL: 10pF, +/-10ppm")
      (libsource (lib "Sandor Lazar") (part "XTAL-2"))
    )
    (comp (ref "Y2")
      (value "8MHz")
      (footprint "Yajingxin TX32258M4DBDD2T-Footprint-1")
      (description "8 MHz crystal, CL: 10pF, +/-10ppm")
      (libsource (lib "Sandor Lazar") (part "XTAL-2"))
    )
    (comp (ref "Y3")
      (value "12MHz")
      (footprint "Yajingxin TX32258M4DBDD2T-Footprint-1")
      (description "8 MHz crystal, CL: 10pF, +/-10ppm")
      (libsource (lib "Sandor Lazar") (part "XTAL-2"))
    )
  )
  (nets
    (net (code "1") (name "+3V3") (class "Default")
      (node (ref "C2") (pin "2") (pinfunction "2_2") (pintype "passive"))
      (node (ref "C20") (pin "2") (pinfunction "2_2") (pintype "passive"))
      (node (ref "C29") (pin "2") (pinfunction "2_2") (pintype "passive"))
      (node (ref "C3") (pin "2") (pinfunction "2_2") (pintype "passive"))
      (node (ref "C32") (pin "2") (pinfunction "2_2") (pintype "passive"))
      (node (ref "C33") (pin "2") (pinfunction "2_2") (pintype "passive"))
      (node (ref "C4") (pin "2") (pinfunction "2_2") (pintype "passive"))
      (node (ref "C5") (pin "2") (pinfunction "2_2") (pintype "passive"))
      (node (ref "C6") (pin "2") (pinfunction "2_2") (pintype "passive"))
      (node (ref "C7") (pin "2") (pinfunction "2_2") (pintype "passive"))
      (node (ref "C8") (pin "2") (pinfunction "2_2") (pintype "passive"))
      (node (ref "D3") (pin "1") (pinfunction "1_1") (pintype "passive"))
      (node (ref "H1") (pin "1") (pinfunction "VCC_1") (pintype "input"))
      (node (ref "IC1") (pin "2") (pinfunction "VOUT_2") (pintype "passive"))
      (node (ref "IC4") (pin "13") (pinfunction "VDDA_13") (pintype "passive"))
      (node (ref "IC4") (pin "9") (pinfunction "VDD_9") (pintype "passive"))
      (node (ref "P1") (pin "2") (pinfunction "2_2") (pintype "passive"))
      (node (ref "P3") (pin "2") (pinfunction "2_2") (pintype "passive"))
      (node (ref "R12") (pin "2") (pinfunction "2_2") (pintype "passive"))
      (node (ref "R20") (pin "2") (pinfunction "2_2") (pintype "passive"))
      (node (ref "R21") (pin "2") (pinfunction "2_2") (pintype "passive"))
      (node (ref "R22") (pin "2") (pinfunction "2_2") (pintype "passive"))
      (node (ref "R24") (pin "2") (pinfunction "2_2") (pintype "passive"))
      (node (ref "R27") (pin "2") (pinfunction "2_2") (pintype "passive"))
      (node (ref "R39") (pin "2") (pinfunction "2_2") (pintype "passive"))
      (node (ref "R8") (pin "2") (pinfunction "2_2") (pintype "passive"))
      (node (ref "S1") (pin "3") (pinfunction "3_3") (pintype "passive"))
      (node (ref "S2") (pin "3") (pinfunction "3_3") (pintype "passive"))
      (node (ref "U1") (pin "1") (pinfunction "VBAT_1") (pintype "power_in"))
      (node (ref "U1") (pin "24") (pinfunction "VDD_1_24") (pintype "power_in"))
      (node (ref "U1") (pin "36") (pinfunction "VDD_2_36") (pintype "power_in"))
      (node (ref "U1") (pin "48") (pinfunction "VDD_3_48") (pintype "power_in"))
      (node (ref "U1") (pin "9") (pinfunction "VDDA_9") (pintype "power_in"))
    )
    (net (code "2") (name "+5V") (class "Default")
      (node (ref "C1") (pin "2") (pinfunction "2_2") (pintype "passive"))
      (node (ref "C14") (pin "2") (pinfunction "2_2") (pintype "passive"))
      (node (ref "C16") (pin "2") (pinfunction "2_2") (pintype "passive"))
      (node (ref "C17") (pin "1") (pinfunction "1_1") (pintype "passive"))
      (node (ref "C18") (pin "2") (pinfunction "2_2") (pintype "passive"))
      (node (ref "C19") (pin "2") (pinfunction "2_2") (pintype "passive"))
      (node (ref "C24") (pin "2") (pinfunction "2_2") (pintype "passive"))
      (node (ref "C26") (pin "2") (pinfunction "2_2") (pintype "passive"))
      (node (ref "C27") (pin "2") (pinfunction "2_2") (pintype "passive"))
      (node (ref "C28") (pin "2") (pinfunction "2_2") (pintype "passive"))
      (node (ref "C45") (pin "2") (pinfunction "2_2") (pintype "passive"))
      (node (ref "IC1") (pin "3") (pinfunction "VIN_3") (pintype "passive"))
      (node (ref "IC2") (pin "19") (pinfunction "VDD5_19") (pintype "power_in"))
      (node (ref "IC3") (pin "8") (pinfunction "VDD5_8") (pintype "passive"))
      (node (ref "IC4") (pin "10") (pinfunction "5V_10") (pintype "passive"))
      (node (ref "P1") (pin "4") (pinfunction "4_4") (pintype "passive"))
      (node (ref "P3") (pin "4") (pinfunction "4_4") (pintype "passive"))
      (node (ref "R4") (pin "1") (pinfunction "1_1") (pintype "passive"))
      (node (ref "R5") (pin "1") (pinfunction "1_1") (pintype "passive"))
      (node (ref "R6") (pin "1") (pinfunction "1_1") (pintype "passive"))
      (node (ref "S1") (pin "1") (pinfunction "1_1") (pintype "passive"))
      (node (ref "S2") (pin "1") (pinfunction "1_1") (pintype "passive"))
      (node (ref "U2") (pin "3") (pinfunction "VDD5_3") (pintype "power_in"))
      (node (ref "U2") (pin "9") (pinfunction "VBUS_9") (pintype "input"))
      (node (ref "U3") (pin "3") (pinfunction "VDD5_3") (pintype "power_in"))
      (node (ref "U3") (pin "9") (pinfunction "VBUS_9") (pintype "input"))
    )
    (net (code "3") (name "+5V_UPSTREAM") (class "Default")
      (node (ref "IC2") (pin "17") (pinfunction "VBUSM_17") (pintype "passive"))
      (node (ref "IC3") (pin "41") (pinfunction "VBUSM_41") (pintype "passive"))
    )
    (net (code "4") (name "+VCARD") (class "Default")
      (node (ref "C46") (pin "2") (pinfunction "2_2") (pintype "passive"))
      (node (ref "IC4") (pin "8") (pinfunction "PMOS_8") (pintype "passive"))
      (node (ref "J1") (pin "4") (pinfunction "VDD_4") (pintype "passive"))
    )
    (net (code "5") (name "/BOOT0") (class "Default")
      (node (ref "R7") (pin "2") (pinfunction "2_2") (pintype "passive"))
      (node (ref "U1") (pin "44") (pinfunction "BOOT0_44") (pintype "passive"))
    )
    (net (code "6") (name "/CLK") (class "Default")
      (node (ref "J1") (pin "5") (pinfunction "CLX_5") (pintype "passive"))
      (node (ref "R23") (pin "2") (pinfunction "2_2") (pintype "passive"))
    )
    (net (code "7") (name "/CMD") (class "Default")
      (node (ref "J1") (pin "3") (pinfunction "CMD_3") (pintype "passive"))
      (node (ref "R25") (pin "2") (pinfunction "2_2") (pintype "passive"))
      (node (ref "R27") (pin "1") (pinfunction "1_1") (pintype "passive"))
    )
    (net (code "8") (name "/D0") (class "Default")
      (node (ref "IC4") (pin "3") (pinfunction "D0_3") (pintype "passive"))
      (node (ref "J1") (pin "7") (pinfunction "DAT0_7") (pintype "passive"))
      (node (ref "R20") (pin "1") (pinfunction "1_1") (pintype "passive"))
    )
    (net (code "9") (name "/D1") (class "Default")
      (node (ref "IC4") (pin "2") (pinfunction "D1_2") (pintype "passive"))
      (node (ref "J1") (pin "8") (pinfunction "DAT1_8") (pintype "passive"))
      (node (ref "R21") (pin "1") (pinfunction "1_1") (pintype "passive"))
    )
    (net (code "10") (name "/D2") (class "Default")
      (node (ref "IC4") (pin "7") (pinfunction "D2_7") (pintype "passive"))
      (node (ref "J1") (pin "1") (pinfunction "DAT2_1") (pintype "passive"))
      (node (ref "R22") (pin "1") (pinfunction "1_1") (pintype "passive"))
    )
    (net (code "11") (name "/D3") (class "Default")
      (node (ref "IC4") (pin "6") (pinfunction "D3_6") (pintype "passive"))
      (node (ref "J1") (pin "2") (pinfunction "CD/DAT3_2") (pintype "passive"))
      (node (ref "R24") (pin "1") (pinfunction "1_1") (pintype "passive"))
    )
    (net (code "12") (name "/DRV") (class "Default")
      (node (ref "IC3") (pin "1") (pinfunction "DRV_1") (pintype "passive"))
      (node (ref "R14") (pin "2") (pinfunction "2_2") (pintype "passive"))
      (node (ref "R15") (pin "2") (pinfunction "2_2") (pintype "passive"))
      (node (ref "R16") (pin "2") (pinfunction "2_2") (pintype "passive"))
      (node (ref "R17") (pin "2") (pinfunction "2_2") (pintype "passive"))
      (node (ref "R18") (pin "2") (pinfunction "2_2") (pintype "passive"))
      (node (ref "R19") (pin "2") (pinfunction "2_2") (pintype "passive"))
    )
    (net (code "13") (name "/FE1.1RST") (class "Default")
      (node (ref "IC2") (pin "16") (pinfunction "XRSTJ_16") (pintype "passive"))
      (node (ref "R38") (pin "2") (pinfunction "2_2") (pintype "passive"))
    )
    (net (code "14") (name "/FE1.1_VD33") (class "Default")
      (node (ref "C10") (pin "1") (pinfunction "1_1") (pintype "passive"))
      (node (ref "C9") (pin "2") (pinfunction "2_2") (pintype "passive"))
      (node (ref "IC2") (pin "1") (pinfunction "OVCJ_1") (pintype "passive"))
      (node (ref "IC2") (pin "18") (pinfunction "BUSJ_18") (pintype "passive"))
      (node (ref "IC2") (pin "20") (pinfunction "VD33F_20") (pintype "power_in"))
      (node (ref "R38") (pin "1") (pinfunction "1_1") (pintype "passive"))
    )
    (net (code "15") (name "/FE2.1_VD18") (class "Default")
      (node (ref "C35") (pin "2") (pinfunction "2_2") (pintype "passive"))
      (node (ref "C42") (pin "1") (pinfunction "1_1") (pintype "passive"))
      (node (ref "C43") (pin "1") (pinfunction "1_1") (pintype "passive"))
      (node (ref "C44") (pin "1") (pinfunction "1_1") (pintype "passive"))
      (node (ref "IC3") (pin "21") (pinfunction "VD_PLL_21") (pintype "passive"))
      (node (ref "IC3") (pin "25") (pinfunction "VD18_O_25") (pintype "passive"))
      (node (ref "IC3") (pin "28") (pinfunction "VD18_2_28") (pintype "passive"))
      (node (ref "IC3") (pin "6") (pinfunction "VD18_1_6") (pintype "passive"))
    )
    (net (code "16") (name "/FE2.1_VD33") (class "Default")
      (node (ref "C34") (pin "2") (pinfunction "2_2") (pintype "passive"))
      (node (ref "C36") (pin "1") (pinfunction "1_1") (pintype "passive"))
      (node (ref "C37") (pin "1") (pinfunction "1_1") (pintype "passive"))
      (node (ref "C38") (pin "1") (pinfunction "1_1") (pintype "passive"))
      (node (ref "C39") (pin "1") (pinfunction "1_1") (pintype "passive"))
      (node (ref "C40") (pin "1") (pinfunction "1_1") (pintype "passive"))
      (node (ref "C41") (pin "1") (pinfunction "1_1") (pintype "passive"))
      (node (ref "IC3") (pin "15") (pinfunction "VD33_1_15") (pintype "passive"))
      (node (ref "IC3") (pin "20") (pinfunction "VD33_2_20") (pintype "passive"))
      (node (ref "IC3") (pin "26") (pinfunction "VD33_3_26") (pintype "passive"))
      (node (ref "IC3") (pin "31") (pinfunction "VD33_4_31") (pintype "passive"))
      (node (ref "IC3") (pin "36") (pinfunction "VD33_5_36") (pintype "passive"))
      (node (ref "IC3") (pin "42") (pinfunction "VD33_6_42") (pintype "passive"))
      (node (ref "IC3") (pin "9") (pinfunction "VD33_O_9") (pintype "passive"))
      (node (ref "R26") (pin "1") (pinfunction "1_1") (pintype "passive"))
    )
    (net (code "17") (name "/FE2.2RST") (class "Default")
      (node (ref "IC3") (pin "40") (pinfunction "XRSTJ_40") (pintype "passive"))
      (node (ref "R26") (pin "2") (pinfunction "2_2") (pintype "passive"))
    )
    (net (code "18") (name "/FE2_EN") (class "Default")
      (node (ref "IC3") (pin "44") (pinfunction "PWRJ_44") (pintype "output"))
      (node (ref "R4") (pin "2") (pinfunction "2_2") (pintype "passive"))
    )
    (net (code "19") (name "/FE2_OC1") (class "Default")
      (node (ref "IC3") (pin "45") (pinfunction "OVCJ1_45") (pintype "passive"))
      (node (ref "R5") (pin "2") (pinfunction "2_2") (pintype "passive"))
    )
    (net (code "20") (name "/FE2_OC5") (class "Default")
      (node (ref "IC3") (pin "43") (pinfunction "OVCJ5_43") (pintype "passive"))
      (node (ref "R6") (pin "2") (pinfunction "2_2") (pintype "passive"))
    )
    (net (code "21") (name "/LED_P2") (class "Default")
      (node (ref "D10") (pin "2") (pinfunction "2_2") (pintype "passive"))
      (node (ref "IC3") (pin "4") (pinfunction "LED[2]_4") (pintype "passive"))
    )
    (net (code "22") (name "/LED_P3") (class "Default")
      (node (ref "D9") (pin "2") (pinfunction "2_2") (pintype "passive"))
      (node (ref "IC3") (pin "5") (pinfunction "LED[3]_5") (pintype "passive"))
    )
    (net (code "23") (name "/LED_P4") (class "Default")
      (node (ref "D8") (pin "2") (pinfunction "2_2") (pintype "passive"))
      (node (ref "IC3") (pin "7") (pinfunction "LED[4]_7") (pintype "passive"))
    )
    (net (code "24") (name "/LED_P5") (class "Default")
      (node (ref "D7") (pin "2") (pinfunction "2_2") (pintype "passive"))
      (node (ref "IC3") (pin "48") (pinfunction "LED[5]_48") (pintype "passive"))
    )
    (net (code "25") (name "/LED_P6") (class "Default")
      (node (ref "D6") (pin "2") (pinfunction "2_2") (pintype "passive"))
      (node (ref "IC3") (pin "47") (pinfunction "LED[6]_47") (pintype "passive"))
    )
    (net (code "26") (name "/LED_P7") (class "Default")
      (node (ref "D5") (pin "2") (pinfunction "2_2") (pintype "passive"))
      (node (ref "IC3") (pin "46") (pinfunction "LED[7]_46") (pintype "passive"))
    )
    (net (code "27") (name "/NRST") (class "Default")
      (node (ref "H1") (pin "2") (pinfunction "NRST_2") (pintype "input"))
      (node (ref "R8") (pin "1") (pinfunction "1_1") (pintype "passive"))
      (node (ref "U1") (pin "7") (pinfunction "NRST_7") (pintype "bidirectional"))
    )
    (net (code "28") (name "/P1_D_N") (class "Default")
      (node (ref "IC2") (pin "15") (pinfunction "DPU_15") (pintype "passive"))
      (node (ref "IC3") (pin "18") (pinfunction "DM1_18") (pintype "passive"))
    )
    (net (code "29") (name "/P1_D_P") (class "Default")
      (node (ref "IC2") (pin "14") (pinfunction "DMU_14") (pintype "passive"))
      (node (ref "IC3") (pin "19") (pinfunction "DP1_19") (pintype "passive"))
    )
    (net (code "30") (name "/P2_D_N") (class "Default")
      (node (ref "IC3") (pin "16") (pinfunction "DM2_16") (pintype "passive"))
    )
    (net (code "31") (name "/P2_D_P") (class "Default")
      (node (ref "IC3") (pin "17") (pinfunction "DP2_17") (pintype "passive"))
    )
    (net (code "32") (name "/P3_D_N") (class "Default")
      (node (ref "IC3") (pin "13") (pinfunction "DM3_13") (pintype "passive"))
    )
    (net (code "33") (name "/P3_D_P") (class "Default")
      (node (ref "IC3") (pin "14") (pinfunction "DP3_14") (pintype "passive"))
    )
    (net (code "34") (name "/P4_D_N") (class "Default")
      (node (ref "IC3") (pin "11") (pinfunction "DM4_11") (pintype "passive"))
    )
    (net (code "35") (name "/P4_D_P") (class "Default")
      (node (ref "IC3") (pin "12") (pinfunction "DP4_12") (pintype "passive"))
    )
    (net (code "36") (name "/P5_D_N") (class "Default")
      (node (ref "IC3") (pin "32") (pinfunction "DM5_32") (pintype "passive"))
    )
    (net (code "37") (name "/P5_D_P") (class "Default")
      (node (ref "IC3") (pin "33") (pinfunction "DP5_33") (pintype "passive"))
    )
    (net (code "38") (name "/P6_D_N") (class "Default")
      (node (ref "IC3") (pin "34") (pinfunction "DM6_34") (pintype "passive"))
    )
    (net (code "39") (name "/P6_D_P") (class "Default")
      (node (ref "IC3") (pin "35") (pinfunction "DP6_35") (pintype "passive"))
    )
    (net (code "40") (name "/P7_D_N") (class "Default")
      (node (ref "IC3") (pin "37") (pinfunction "DM7_37") (pintype "passive"))
    )
    (net (code "41") (name "/P7_D_P") (class "Default")
      (node (ref "IC3") (pin "38") (pinfunction "DP7_38") (pintype "passive"))
    )
    (net (code "42") (name "/P8_D_N") (class "Default")
      (node (ref "IC2") (pin "11") (pinfunction "DM1_11") (pintype "passive"))
      (node (ref "U2") (pin "8") (pinfunction "UD-_8") (pintype "bidirectional"))
    )
    (net (code "43") (name "/P8_D_P") (class "Default")
      (node (ref "IC2") (pin "12") (pinfunction "DP1_12") (pintype "passive"))
      (node (ref "U2") (pin "7") (pinfunction "UD+_7") (pintype "bidirectional"))
    )
    (net (code "44") (name "/P9_D_N") (class "Default")
      (node (ref "IC2") (pin "9") (pinfunction "DM2_9") (pintype "passive"))
      (node (ref "U3") (pin "8") (pinfunction "UD-_8") (pintype "bidirectional"))
    )
    (net (code "45") (name "/P9_D_P") (class "Default")
      (node (ref "IC2") (pin "10") (pinfunction "DP2_10") (pintype "passive"))
      (node (ref "U3") (pin "7") (pinfunction "UD+_7") (pintype "bidirectional"))
    )
    (net (code "46") (name "/P10_D_N") (class "Default")
      (node (ref "IC2") (pin "7") (pinfunction "DM3_7") (pintype "passive"))
      (node (ref "U1") (pin "32") (pinfunction "PA11_32") (pintype "bidirectional"))
    )
    (net (code "47") (name "/P10_D_P") (class "Default")
      (node (ref "IC2") (pin "8") (pinfunction "DP3_8") (pintype "passive"))
      (node (ref "R39") (pin "1") (pinfunction "1_1") (pintype "passive"))
      (node (ref "U1") (pin "33") (pinfunction "PA12_33") (pintype "bidirectional"))
    )
    (net (code "48") (name "/P11_D_N") (class "Default")
      (node (ref "IC2") (pin "5") (pinfunction "DM4_5") (pintype "passive"))
      (node (ref "IC4") (pin "16") (pinfunction "DM_16") (pintype "passive"))
    )
    (net (code "49") (name "/P11_D_P") (class "Default")
      (node (ref "IC2") (pin "6") (pinfunction "DP4_6") (pintype "passive"))
      (node (ref "IC4") (pin "15") (pinfunction "DP_15") (pintype "passive"))
    )
    (net (code "50") (name "/RTS1") (class "Default")
      (node (ref "P1") (pin "5") (pinfunction "5_5") (pintype "passive"))
      (node (ref "U2") (pin "13") (pinfunction "RTS_13") (pintype "output"))
    )
    (net (code "51") (name "/RTS2") (class "Default")
      (node (ref "P3") (pin "5") (pinfunction "5_5") (pintype "passive"))
      (node (ref "U3") (pin "13") (pinfunction "RTS_13") (pintype "output"))
    )
    (net (code "52") (name "/RX1") (class "Default")
      (node (ref "P1") (pin "1") (pinfunction "1_1") (pintype "passive"))
      (node (ref "U2") (pin "5") (pinfunction "RXD_5") (pintype "passive"))
    )
    (net (code "53") (name "/RX2") (class "Default")
      (node (ref "P3") (pin "1") (pinfunction "1_1") (pintype "passive"))
      (node (ref "U3") (pin "5") (pinfunction "RXD_5") (pintype "passive"))
    )
    (net (code "54") (name "/STLINK_LED") (class "Default")
      (node (ref "R11") (pin "1") (pinfunction "1_1") (pintype "passive"))
      (node (ref "R13") (pin "1") (pinfunction "1_1") (pintype "passive"))
      (node (ref "U1") (pin "30") (pinfunction "PA9_30") (pintype "bidirectional"))
    )
    (net (code "55") (name "/STLINK_NRST") (class "Default")
      (node (ref "P2") (pin "4") (pinfunction "VCC_4") (pintype "passive"))
      (node (ref "R12") (pin "1") (pinfunction "1_1") (pintype "passive"))
      (node (ref "U1") (pin "18") (pinfunction "PB0_18") (pintype "bidirectional"))
    )
    (net (code "56") (name "/STLINK_SWCLK") (class "Default")
      (node (ref "P2") (pin "2") (pinfunction "RXI_2") (pintype "passive"))
      (node (ref "U1") (pin "15") (pinfunction "PA5_15") (pintype "bidirectional"))
      (node (ref "U1") (pin "26") (pinfunction "PB13_26") (pintype "bidirectional"))
    )
    (net (code "57") (name "/STLINK_SWDIO") (class "Default")
      (node (ref "P2") (pin "1") (pinfunction "DTR_1") (pintype "passive"))
      (node (ref "R3") (pin "1") (pinfunction "1_1") (pintype "passive"))
      (node (ref "U1") (pin "27") (pinfunction "PB14_27") (pintype "bidirectional"))
    )
    (net (code "58") (name "/STLINK_SWO") (class "Default")
      (node (ref "P2") (pin "3") (pinfunction "TXO_3") (pintype "passive"))
      (node (ref "U1") (pin "16") (pinfunction "PA6_16") (pintype "bidirectional"))
    )
    (net (code "59") (name "/SWCLK") (class "Default")
      (node (ref "H1") (pin "5") (pinfunction "CLK_5") (pintype "input"))
      (node (ref "U1") (pin "37") (pinfunction "PA14_37") (pintype "bidirectional"))
    )
    (net (code "60") (name "/SWDIO") (class "Default")
      (node (ref "H1") (pin "4") (pinfunction "SWO_4") (pintype "input"))
      (node (ref "U1") (pin "34") (pinfunction "PA13_34") (pintype "bidirectional"))
    )
    (net (code "61") (name "/SWO") (class "Default")
      (node (ref "H1") (pin "6") (pinfunction "DIO_6") (pintype "input"))
      (node (ref "U1") (pin "39") (pinfunction "PB3_39") (pintype "bidirectional"))
    )
    (net (code "62") (name "/TX1") (class "Default")
      (node (ref "P1") (pin "3") (pinfunction "3_3") (pintype "passive"))
      (node (ref "U2") (pin "4") (pinfunction "TXD_4") (pintype "passive"))
    )
    (net (code "63") (name "/TX2") (class "Default")
      (node (ref "P3") (pin "3") (pinfunction "3_3") (pintype "passive"))
      (node (ref "U3") (pin "4") (pinfunction "TXD_4") (pintype "passive"))
    )
    (net (code "64") (name "/UP_D_N") (class "Default")
      (node (ref "IC3") (pin "29") (pinfunction "DMU_29") (pintype "passive"))
    )
    (net (code "65") (name "/UP_D_P") (class "Default")
      (node (ref "IC3") (pin "30") (pinfunction "DPU_30") (pintype "passive"))
    )
    (net (code "66") (name "/VIO1") (class "Default")
      (node (ref "C15") (pin "1") (pinfunction "1_1") (pintype "passive"))
      (node (ref "R2") (pin "2") (pinfunction "2_2") (pintype "passive"))
      (node (ref "S1") (pin "2") (pinfunction "2_2") (pintype "passive"))
      (node (ref "U2") (pin "1") (pinfunction "VIO_1") (pintype "power_in"))
    )
    (net (code "67") (name "/VIO2") (class "Default")
      (node (ref "C25") (pin "1") (pinfunction "1_1") (pintype "passive"))
      (node (ref "R9") (pin "2") (pinfunction "2_2") (pintype "passive"))
      (node (ref "S2") (pin "2") (pinfunction "2_2") (pintype "passive"))
      (node (ref "U3") (pin "1") (pinfunction "VIO_1") (pintype "power_in"))
    )
    (net (code "68") (name "/XTAL1_IN") (class "Default")
      (node (ref "C30") (pin "2") (pinfunction "2_2") (pintype "passive"))
      (node (ref "IC3") (pin "22") (pinfunction "XIN_22") (pintype "passive"))
      (node (ref "Y3") (pin "1") (pinfunction "1_1") (pintype "passive"))
    )
    (net (code "69") (name "/XTAL1_OUT") (class "Default")
      (node (ref "C31") (pin "2") (pinfunction "2_2") (pintype "passive"))
      (node (ref "IC3") (pin "23") (pinfunction "XOUT_23") (pintype "passive"))
      (node (ref "Y3") (pin "3") (pinfunction "3_3") (pintype "passive"))
    )
    (net (code "70") (name "/XTAL2_IN") (class "Default")
      (node (ref "C13") (pin "1") (pinfunction "1_1") (pintype "passive"))
      (node (ref "IC2") (pin "4") (pinfunction "XIN_4") (pintype "passive"))
      (node (ref "Y1") (pin "1") (pinfunction "1_1") (pintype "passive"))
    )
    (net (code "71") (name "/XTAL2_OUT") (class "Default")
      (node (ref "C11") (pin "1") (pinfunction "1_1") (pintype "passive"))
      (node (ref "IC2") (pin "3") (pinfunction "XOUT_3") (pintype "passive"))
      (node (ref "Y1") (pin "3") (pinfunction "3_3") (pintype "passive"))
    )
    (net (code "72") (name "/XTAL3_IN") (class "Default")
      (node (ref "C22") (pin "2") (pinfunction "2_2") (pintype "passive"))
      (node (ref "U1") (pin "5") (pinfunction "PD0-OSC_IN_5") (pintype "bidirectional"))
      (node (ref "Y2") (pin "3") (pinfunction "3_3") (pintype "passive"))
    )
    (net (code "73") (name "/XTAL3_OUT") (class "Default")
      (node (ref "C23") (pin "2") (pinfunction "2_2") (pintype "passive"))
      (node (ref "U1") (pin "6") (pinfunction "PD1-OSC_OUT_6") (pintype "bidirectional"))
      (node (ref "Y2") (pin "1") (pinfunction "1_1") (pintype "passive"))
    )
    (net (code "74") (name "GND") (class "Default")
      (node (ref "C1") (pin "1") (pinfunction "1_1") (pintype "passive"))
      (node (ref "C10") (pin "2") (pinfunction "2_2") (pintype "passive"))
      (node (ref "C11") (pin "2") (pinfunction "2_2") (pintype "passive"))
      (node (ref "C12") (pin "1") (pinfunction "1_1") (pintype "passive"))
      (node (ref "C13") (pin "2") (pinfunction "2_2") (pintype "passive"))
      (node (ref "C14") (pin "1") (pinfunction "1_1") (pintype "passive"))
      (node (ref "C15") (pin "2") (pinfunction "2_2") (pintype "passive"))
      (node (ref "C16") (pin "1") (pinfunction "1_1") (pintype "passive"))
      (node (ref "C17") (pin "2") (pinfunction "2_2") (pintype "passive"))
      (node (ref "C18") (pin "1") (pinfunction "1_1") (pintype "passive"))
      (node (ref "C19") (pin "1") (pinfunction "1_1") (pintype "passive"))
      (node (ref "C2") (pin "1") (pinfunction "1_1") (pintype "passive"))
      (node (ref "C20") (pin "1") (pinfunction "1_1") (pintype "passive"))
      (node (ref "C21") (pin "1") (pinfunction "1_1") (pintype "passive"))
      (node (ref "C22") (pin "1") (pinfunction "1_1") (pintype "passive"))
      (node (ref "C23") (pin "1") (pinfunction "1_1") (pintype "passive"))
      (node (ref "C24") (pin "1") (pinfunction "1_1") (pintype "passive"))
      (node (ref "C25") (pin "2") (pinfunction "2_2") (pintype "passive"))
      (node (ref "C26") (pin "1") (pinfunction "1_1") (pintype "passive"))
      (node (ref "C27") (pin "1") (pinfunction "1_1") (pintype "passive"))
      (node (ref "C28") (pin "1") (pinfunction "1_1") (pintype "passive"))
      (node (ref "C29") (pin "1") (pinfunction "1_1") (pintype "passive"))
      (node (ref "C3") (pin "1") (pinfunction "1_1") (pintype "passive"))
      (node (ref "C30") (pin "1") (pinfunction "1_1") (pintype "passive"))
      (node (ref "C31") (pin "1") (pinfunction "1_1") (pintype "passive"))
      (node (ref "C32") (pin "1") (pinfunction "1_1") (pintype "passive"))
      (node (ref "C33") (pin "1") (pinfunction "1_1") (pintype "passive"))
      (node (ref "C34") (pin "1") (pinfunction "1_1") (pintype "passive"))
      (node (ref "C35") (pin "1") (pinfunction "1_1") (pintype "passive"))
      (node (ref "C36") (pin "2") (pinfunction "2_2") (pintype "passive"))
      (node (ref "C37") (pin "2") (pinfunction "2_2") (pintype "passive"))
      (node (ref "C38") (pin "2") (pinfunction "2_2") (pintype "passive"))
      (node (ref "C39") (pin "2") (pinfunction "2_2") (pintype "passive"))
      (node (ref "C4") (pin "1") (pinfunction "1_1") (pintype "passive"))
      (node (ref "C40") (pin "2") (pinfunction "2_2") (pintype "passive"))
      (node (ref "C41") (pin "2") (pinfunction "2_2") (pintype "passive"))
      (node (ref "C42") (pin "2") (pinfunction "2_2") (pintype "passive"))
      (node (ref "C43") (pin "2") (pinfunction "2_2") (pintype "passive"))
      (node (ref "C44") (pin "2") (pinfunction "2_2") (pintype "passive"))
      (node (ref "C45") (pin "1") (pinfunction "1_1") (pintype "passive"))
      (node (ref "C46") (pin "1") (pinfunction "1_1") (pintype "passive"))
      (node (ref "C5") (pin "1") (pinfunction "1_1") (pintype "passive"))
      (node (ref "C6") (pin "1") (pinfunction "1_1") (pintype "passive"))
      (node (ref "C7") (pin "1") (pinfunction "1_1") (pintype "passive"))
      (node (ref "C8") (pin "1") (pinfunction "1_1") (pintype "passive"))
      (node (ref "C9") (pin "1") (pinfunction "1_1") (pintype "passive"))
      (node (ref "D4") (pin "2") (pinfunction "2_2") (pintype "passive"))
      (node (ref "H1") (pin "3") (pinfunction "GND_3") (pintype "input"))
      (node (ref "IC1") (pin "1") (pinfunction "GND_1") (pintype "passive"))
      (node (ref "IC1") (pin "4") (pinfunction "NC_4") (pintype "passive"))
      (node (ref "IC2") (pin "25") (pinfunction "VSS_25") (pintype "power_in"))
      (node (ref "IC3") (pin "10") (pinfunction "VSS_1_10") (pintype "passive"))
      (node (ref "IC3") (pin "24") (pinfunction "VS_PLL_24") (pintype "passive"))
      (node (ref "IC3") (pin "39") (pinfunction "VSS_2_39") (pintype "passive"))
      (node (ref "IC4") (pin "1") (pinfunction "VSS_1_1") (pintype "passive"))
      (node (ref "IC4") (pin "14") (pinfunction "VSS_2_14") (pintype "passive"))
      (node (ref "J1") (pin "6") (pinfunction "VSS_6") (pintype "passive"))
      (node (ref "J1") (pin "G1") (pinfunction "MP_1_G1") (pintype "passive"))
      (node (ref "J1") (pin "G2") (pinfunction "MP_2_G2") (pintype "passive"))
      (node (ref "J1") (pin "G3") (pinfunction "MP_3_G3") (pintype "passive"))
      (node (ref "J1") (pin "G4") (pinfunction "MP_4_G4") (pintype "passive"))
      (node (ref "P1") (pin "6") (pinfunction "6_6") (pintype "passive"))
      (node (ref "P2") (pin "5") (pinfunction "CTS_5") (pintype "passive"))
      (node (ref "P3") (pin "6") (pinfunction "6_6") (pintype "passive"))
      (node (ref "R1") (pin "2") (pinfunction "2_2") (pintype "passive"))
      (node (ref "R10") (pin "2") (pinfunction "2_2") (pintype "passive"))
      (node (ref "R7") (pin "1") (pinfunction "1_1") (pintype "passive"))
      (node (ref "U1") (pin "23") (pinfunction "VSS_1_23") (pintype "power_in"))
      (node (ref "U1") (pin "35") (pinfunction "VSS_2_35") (pintype "power_in"))
      (node (ref "U1") (pin "47") (pinfunction "VSS_3_47") (pintype "power_in"))
      (node (ref "U1") (pin "8") (pinfunction "VSSA_8") (pintype "power_in"))
      (node (ref "U2") (pin "17") (pinfunction "GND_17") (pintype "power_in"))
      (node (ref "U2") (pin "2") (pinfunction "GND_2") (pintype "power_in"))
      (node (ref "U3") (pin "17") (pinfunction "GND_17") (pintype "power_in"))
      (node (ref "U3") (pin "2") (pinfunction "GND_2") (pintype "power_in"))
      (node (ref "Y1") (pin "2") (pinfunction "GND_2") (pintype "passive"))
      (node (ref "Y1") (pin "4") (pinfunction "GND_4") (pintype "passive"))
      (node (ref "Y2") (pin "2") (pinfunction "GND_2") (pintype "passive"))
      (node (ref "Y2") (pin "4") (pinfunction "GND_4") (pintype "passive"))
      (node (ref "Y3") (pin "2") (pinfunction "GND_2") (pintype "passive"))
      (node (ref "Y3") (pin "4") (pinfunction "GND_4") (pintype "passive"))
    )
    (net (code "75") (name "Net-(D1-Pad1)") (class "Default")
      (node (ref "D1") (pin "1") (pinfunction "1_1") (pintype "passive"))
      (node (ref "R2") (pin "1") (pinfunction "1_1") (pintype "passive"))
    )
    (net (code "76") (name "Net-(D2-Pad1)") (class "Default")
      (node (ref "D2") (pin "1") (pinfunction "1_1") (pintype "passive"))
      (node (ref "R9") (pin "1") (pinfunction "1_1") (pintype "passive"))
    )
    (net (code "77") (name "Net-(D3-Pad2)") (class "Default")
      (node (ref "D3") (pin "2") (pinfunction "2_2") (pintype "passive"))
      (node (ref "R11") (pin "2") (pinfunction "2_2") (pintype "passive"))
    )
    (net (code "78") (name "Net-(D4-Pad1)") (class "Default")
      (node (ref "D4") (pin "1") (pinfunction "1_1") (pintype "passive"))
      (node (ref "R13") (pin "2") (pinfunction "2_2") (pintype "passive"))
    )
    (net (code "79") (name "Net-(D5-Pad1)") (class "Default")
      (node (ref "D5") (pin "1") (pinfunction "1_1") (pintype "passive"))
      (node (ref "R14") (pin "1") (pinfunction "1_1") (pintype "passive"))
    )
    (net (code "80") (name "Net-(D6-Pad1)") (class "Default")
      (node (ref "D6") (pin "1") (pinfunction "1_1") (pintype "passive"))
      (node (ref "R15") (pin "1") (pinfunction "1_1") (pintype "passive"))
    )
    (net (code "81") (name "Net-(D7-Pad1)") (class "Default")
      (node (ref "D7") (pin "1") (pinfunction "1_1") (pintype "passive"))
      (node (ref "R16") (pin "1") (pinfunction "1_1") (pintype "passive"))
    )
    (net (code "82") (name "Net-(D8-Pad1)") (class "Default")
      (node (ref "D8") (pin "1") (pinfunction "1_1") (pintype "passive"))
      (node (ref "R17") (pin "1") (pinfunction "1_1") (pintype "passive"))
    )
    (net (code "83") (name "Net-(D9-Pad1)") (class "Default")
      (node (ref "D9") (pin "1") (pinfunction "1_1") (pintype "passive"))
      (node (ref "R18") (pin "1") (pinfunction "1_1") (pintype "passive"))
    )
    (net (code "84") (name "Net-(D10-Pad1)") (class "Default")
      (node (ref "D10") (pin "1") (pinfunction "1_1") (pintype "passive"))
      (node (ref "R19") (pin "1") (pinfunction "1_1") (pintype "passive"))
    )
    (net (code "85") (name "Net-(IC2-REXT)") (class "Default")
      (node (ref "IC2") (pin "13") (pinfunction "REXT_13") (pintype "passive"))
      (node (ref "R1") (pin "1") (pinfunction "1_1") (pintype "passive"))
    )
    (net (code "86") (name "Net-(IC3-REXT)") (class "Default")
      (node (ref "IC3") (pin "27") (pinfunction "REXT_27") (pintype "passive"))
      (node (ref "R10") (pin "1") (pinfunction "1_1") (pintype "passive"))
    )
    (net (code "87") (name "Net-(IC4-CLK)") (class "Default")
      (node (ref "IC4") (pin "4") (pinfunction "CLK_4") (pintype "passive"))
      (node (ref "R23") (pin "1") (pinfunction "1_1") (pintype "passive"))
    )
    (net (code "88") (name "Net-(IC4-CMD)") (class "Default")
      (node (ref "IC4") (pin "5") (pinfunction "CMD_5") (pintype "passive"))
      (node (ref "R25") (pin "1") (pinfunction "1_1") (pintype "passive"))
    )
    (net (code "89") (name "Net-(U1A-PB12)") (class "Default")
      (node (ref "R3") (pin "2") (pinfunction "2_2") (pintype "passive"))
      (node (ref "U1") (pin "25") (pinfunction "PB12_25") (pintype "bidirectional"))
    )
    (net (code "90") (name "Net-(U2-V3)") (class "Default")
      (node (ref "C12") (pin "2") (pinfunction "2_2") (pintype "passive"))
      (node (ref "U2") (pin "6") (pinfunction "V3_6") (pintype "power_in"))
    )
    (net (code "91") (name "Net-(U2-~{ACT})") (class "Default")
      (node (ref "D1") (pin "2") (pinfunction "2_2") (pintype "passive"))
      (node (ref "U2") (pin "10") (pinfunction "~{ACT}_10") (pintype "output"))
    )
    (net (code "92") (name "Net-(U3-V3)") (class "Default")
      (node (ref "C21") (pin "2") (pinfunction "2_2") (pintype "passive"))
      (node (ref "U3") (pin "6") (pinfunction "V3_6") (pintype "power_in"))
    )
    (net (code "93") (name "Net-(U3-~{ACT})") (class "Default")
      (node (ref "D2") (pin "2") (pinfunction "2_2") (pintype "passive"))
      (node (ref "U3") (pin "10") (pinfunction "~{ACT}_10") (pintype "output"))
    )
    (net (code "94") (name "unconnected-(IC2-DRV-Pad21)") (class "Default")
      (node (ref "IC2") (pin "21") (pinfunction "DRV_21") (pintype "passive"))
    )
    (net (code "95") (name "unconnected-(IC2-LED1-Pad22)") (class "Default")
      (node (ref "IC2") (pin "22") (pinfunction "LED1_22") (pintype "passive+no_connect"))
    )
    (net (code "96") (name "unconnected-(IC2-LED2-Pad23)") (class "Default")
      (node (ref "IC2") (pin "23") (pinfunction "LED2_23") (pintype "passive+no_connect"))
    )
    (net (code "97") (name "unconnected-(IC2-PWRJ-Pad24)") (class "Default")
      (node (ref "IC2") (pin "24") (pinfunction "PWRJ_24") (pintype "passive+no_connect"))
    )
    (net (code "98") (name "unconnected-(IC2-TESTJ-Pad2)") (class "Default")
      (node (ref "IC2") (pin "2") (pinfunction "TESTJ_2") (pintype "passive+no_connect"))
    )
    (net (code "99") (name "unconnected-(IC3-LED[1]-Pad3)") (class "Default")
      (node (ref "IC3") (pin "3") (pinfunction "LED[1]_3") (pintype "passive+no_connect"))
    )
    (net (code "100") (name "unconnected-(IC3-TESTJ-Pad2)") (class "Default")
      (node (ref "IC3") (pin "2") (pinfunction "TESTJ_2") (pintype "passive+no_connect"))
    )
    (net (code "101") (name "unconnected-(IC4-GPIO-Pad11)") (class "Default")
      (node (ref "IC4") (pin "11") (pinfunction "GPIO_11") (pintype "passive+no_connect"))
    )
    (net (code "102") (name "unconnected-(IC4-LED-Pad12)") (class "Default")
      (node (ref "IC4") (pin "12") (pinfunction "LED_12") (pintype "passive+no_connect"))
    )
    (net (code "103") (name "unconnected-(J1-CD-PadCD1)") (class "Default")
      (node (ref "J1") (pin "CD1") (pinfunction "CD_CD1") (pintype "passive+no_connect"))
    )
    (net (code "104") (name "unconnected-(S1-PadMH1)") (class "Default")
      (node (ref "S1") (pin "MH1") (pinfunction "MH1_MH1") (pintype "passive+no_connect"))
    )
    (net (code "105") (name "unconnected-(S1-PadMH2)") (class "Default")
      (node (ref "S1") (pin "MH2") (pinfunction "MH2_MH2") (pintype "passive+no_connect"))
    )
    (net (code "106") (name "unconnected-(S2-PadMH1)") (class "Default")
      (node (ref "S2") (pin "MH1") (pinfunction "MH1_MH1") (pintype "passive+no_connect"))
    )
    (net (code "107") (name "unconnected-(S2-PadMH2)") (class "Default")
      (node (ref "S2") (pin "MH2") (pinfunction "MH2_MH2") (pintype "passive+no_connect"))
    )
    (net (code "108") (name "unconnected-(ST1-H1-Pad1)") (class "Default")
      (node (ref "ST1") (pin "1") (pinfunction "H1_1") (pintype "passive+no_connect"))
    )
    (net (code "109") (name "unconnected-(ST2-H1-Pad1)") (class "Default")
      (node (ref "ST2") (pin "1") (pinfunction "H1_1") (pintype "passive+no_connect"))
    )
    (net (code "110") (name "unconnected-(ST3-H1-Pad1)") (class "Default")
      (node (ref "ST3") (pin "1") (pinfunction "H1_1") (pintype "passive+no_connect"))
    )
    (net (code "111") (name "unconnected-(ST4-H1-Pad1)") (class "Default")
      (node (ref "ST4") (pin "1") (pinfunction "H1_1") (pintype "passive+no_connect"))
    )
    (net (code "112") (name "unconnected-(U1A-PA0-WKUP-Pad10)") (class "Default")
      (node (ref "U1") (pin "10") (pinfunction "PA0-WKUP_10") (pintype "bidirectional+no_connect"))
    )
    (net (code "113") (name "unconnected-(U1A-PA1-Pad11)") (class "Default")
      (node (ref "U1") (pin "11") (pinfunction "PA1_11") (pintype "bidirectional+no_connect"))
    )
    (net (code "114") (name "unconnected-(U1A-PA2-Pad12)") (class "Default")
      (node (ref "U1") (pin "12") (pinfunction "PA2_12") (pintype "bidirectional+no_connect"))
    )
    (net (code "115") (name "unconnected-(U1A-PA3-Pad13)") (class "Default")
      (node (ref "U1") (pin "13") (pinfunction "PA3_13") (pintype "bidirectional+no_connect"))
    )
    (net (code "116") (name "unconnected-(U1A-PA4-Pad14)") (class "Default")
      (node (ref "U1") (pin "14") (pinfunction "PA4_14") (pintype "bidirectional+no_connect"))
    )
    (net (code "117") (name "unconnected-(U1A-PA7-Pad17)") (class "Default")
      (node (ref "U1") (pin "17") (pinfunction "PA7_17") (pintype "bidirectional+no_connect"))
    )
    (net (code "118") (name "unconnected-(U1A-PA8-Pad29)") (class "Default")
      (node (ref "U1") (pin "29") (pinfunction "PA8_29") (pintype "bidirectional+no_connect"))
    )
    (net (code "119") (name "unconnected-(U1A-PA10-Pad31)") (class "Default")
      (node (ref "U1") (pin "31") (pinfunction "PA10_31") (pintype "bidirectional"))
    )
    (net (code "120") (name "unconnected-(U1A-PA15-Pad38)") (class "Default")
      (node (ref "U1") (pin "38") (pinfunction "PA15_38") (pintype "bidirectional+no_connect"))
    )
    (net (code "121") (name "unconnected-(U1A-PB1-Pad19)") (class "Default")
      (node (ref "U1") (pin "19") (pinfunction "PB1_19") (pintype "bidirectional+no_connect"))
    )
    (net (code "122") (name "unconnected-(U1A-PB2-Pad20)") (class "Default")
      (node (ref "U1") (pin "20") (pinfunction "PB2_20") (pintype "bidirectional+no_connect"))
    )
    (net (code "123") (name "unconnected-(U1A-PB4-Pad40)") (class "Default")
      (node (ref "U1") (pin "40") (pinfunction "PB4_40") (pintype "bidirectional+no_connect"))
    )
    (net (code "124") (name "unconnected-(U1A-PB5-Pad41)") (class "Default")
      (node (ref "U1") (pin "41") (pinfunction "PB5_41") (pintype "bidirectional+no_connect"))
    )
    (net (code "125") (name "unconnected-(U1A-PB6-Pad42)") (class "Default")
      (node (ref "U1") (pin "42") (pinfunction "PB6_42") (pintype "bidirectional+no_connect"))
    )
    (net (code "126") (name "unconnected-(U1A-PB7-Pad43)") (class "Default")
      (node (ref "U1") (pin "43") (pinfunction "PB7_43") (pintype "bidirectional+no_connect"))
    )
    (net (code "127") (name "unconnected-(U1A-PB8-Pad45)") (class "Default")
      (node (ref "U1") (pin "45") (pinfunction "PB8_45") (pintype "bidirectional+no_connect"))
    )
    (net (code "128") (name "unconnected-(U1A-PB9-Pad46)") (class "Default")
      (node (ref "U1") (pin "46") (pinfunction "PB9_46") (pintype "bidirectional+no_connect"))
    )
    (net (code "129") (name "unconnected-(U1A-PB10-Pad21)") (class "Default")
      (node (ref "U1") (pin "21") (pinfunction "PB10_21") (pintype "bidirectional+no_connect"))
    )
    (net (code "130") (name "unconnected-(U1A-PB11-Pad22)") (class "Default")
      (node (ref "U1") (pin "22") (pinfunction "PB11_22") (pintype "bidirectional+no_connect"))
    )
    (net (code "131") (name "unconnected-(U1A-PB15-Pad28)") (class "Default")
      (node (ref "U1") (pin "28") (pinfunction "PB15_28") (pintype "bidirectional+no_connect"))
    )
    (net (code "132") (name "unconnected-(U1A-PC13-TAMPER-RTC-Pad2)") (class "Default")
      (node (ref "U1") (pin "2") (pinfunction "PC13-TAMPER-RTC_2") (pintype "bidirectional+no_connect"))
    )
    (net (code "133") (name "unconnected-(U1A-PC14-OSC32_IN-Pad3)") (class "Default")
      (node (ref "U1") (pin "3") (pinfunction "PC14-OSC32_IN_3") (pintype "bidirectional+no_connect"))
    )
    (net (code "134") (name "unconnected-(U1A-PC15-OSC32_OUT-Pad4)") (class "Default")
      (node (ref "U1") (pin "4") (pinfunction "PC15-OSC32_OUT_4") (pintype "bidirectional+no_connect"))
    )
    (net (code "135") (name "unconnected-(U2-CTS-Pad15)") (class "Default")
      (node (ref "U2") (pin "15") (pinfunction "CTS_15") (pintype "input+no_connect"))
    )
    (net (code "136") (name "unconnected-(U2-DCD-Pad11)") (class "Default")
      (node (ref "U2") (pin "11") (pinfunction "DCD_11") (pintype "input+no_connect"))
    )
    (net (code "137") (name "unconnected-(U2-DSR-Pad14)") (class "Default")
      (node (ref "U2") (pin "14") (pinfunction "DSR_14") (pintype "input+no_connect"))
    )
    (net (code "138") (name "unconnected-(U2-DTR-Pad12)") (class "Default")
      (node (ref "U2") (pin "12") (pinfunction "DTR_12") (pintype "output+no_connect"))
    )
    (net (code "139") (name "unconnected-(U2-RI-Pad16)") (class "Default")
      (node (ref "U2") (pin "16") (pinfunction "RI_16") (pintype "input+no_connect"))
    )
    (net (code "140") (name "unconnected-(U3-CTS-Pad15)") (class "Default")
      (node (ref "U3") (pin "15") (pinfunction "CTS_15") (pintype "input+no_connect"))
    )
    (net (code "141") (name "unconnected-(U3-DCD-Pad11)") (class "Default")
      (node (ref "U3") (pin "11") (pinfunction "DCD_11") (pintype "input+no_connect"))
    )
    (net (code "142") (name "unconnected-(U3-DSR-Pad14)") (class "Default")
      (node (ref "U3") (pin "14") (pinfunction "DSR_14") (pintype "input+no_connect"))
    )
    (net (code "143") (name "unconnected-(U3-DTR-Pad12)") (class "Default")
      (node (ref "U3") (pin "12") (pinfunction "DTR_12") (pintype "output+no_connect"))
    )
    (net (code "144") (name "unconnected-(U3-RI-Pad16)") (class "Default")
      (node (ref "U3") (pin "16") (pinfunction "RI_16") (pintype "input+no_connect"))
    )
  )
)
